# DNVT_box3rt.net
KiCad netlist of a schematic drawn in EAGLE
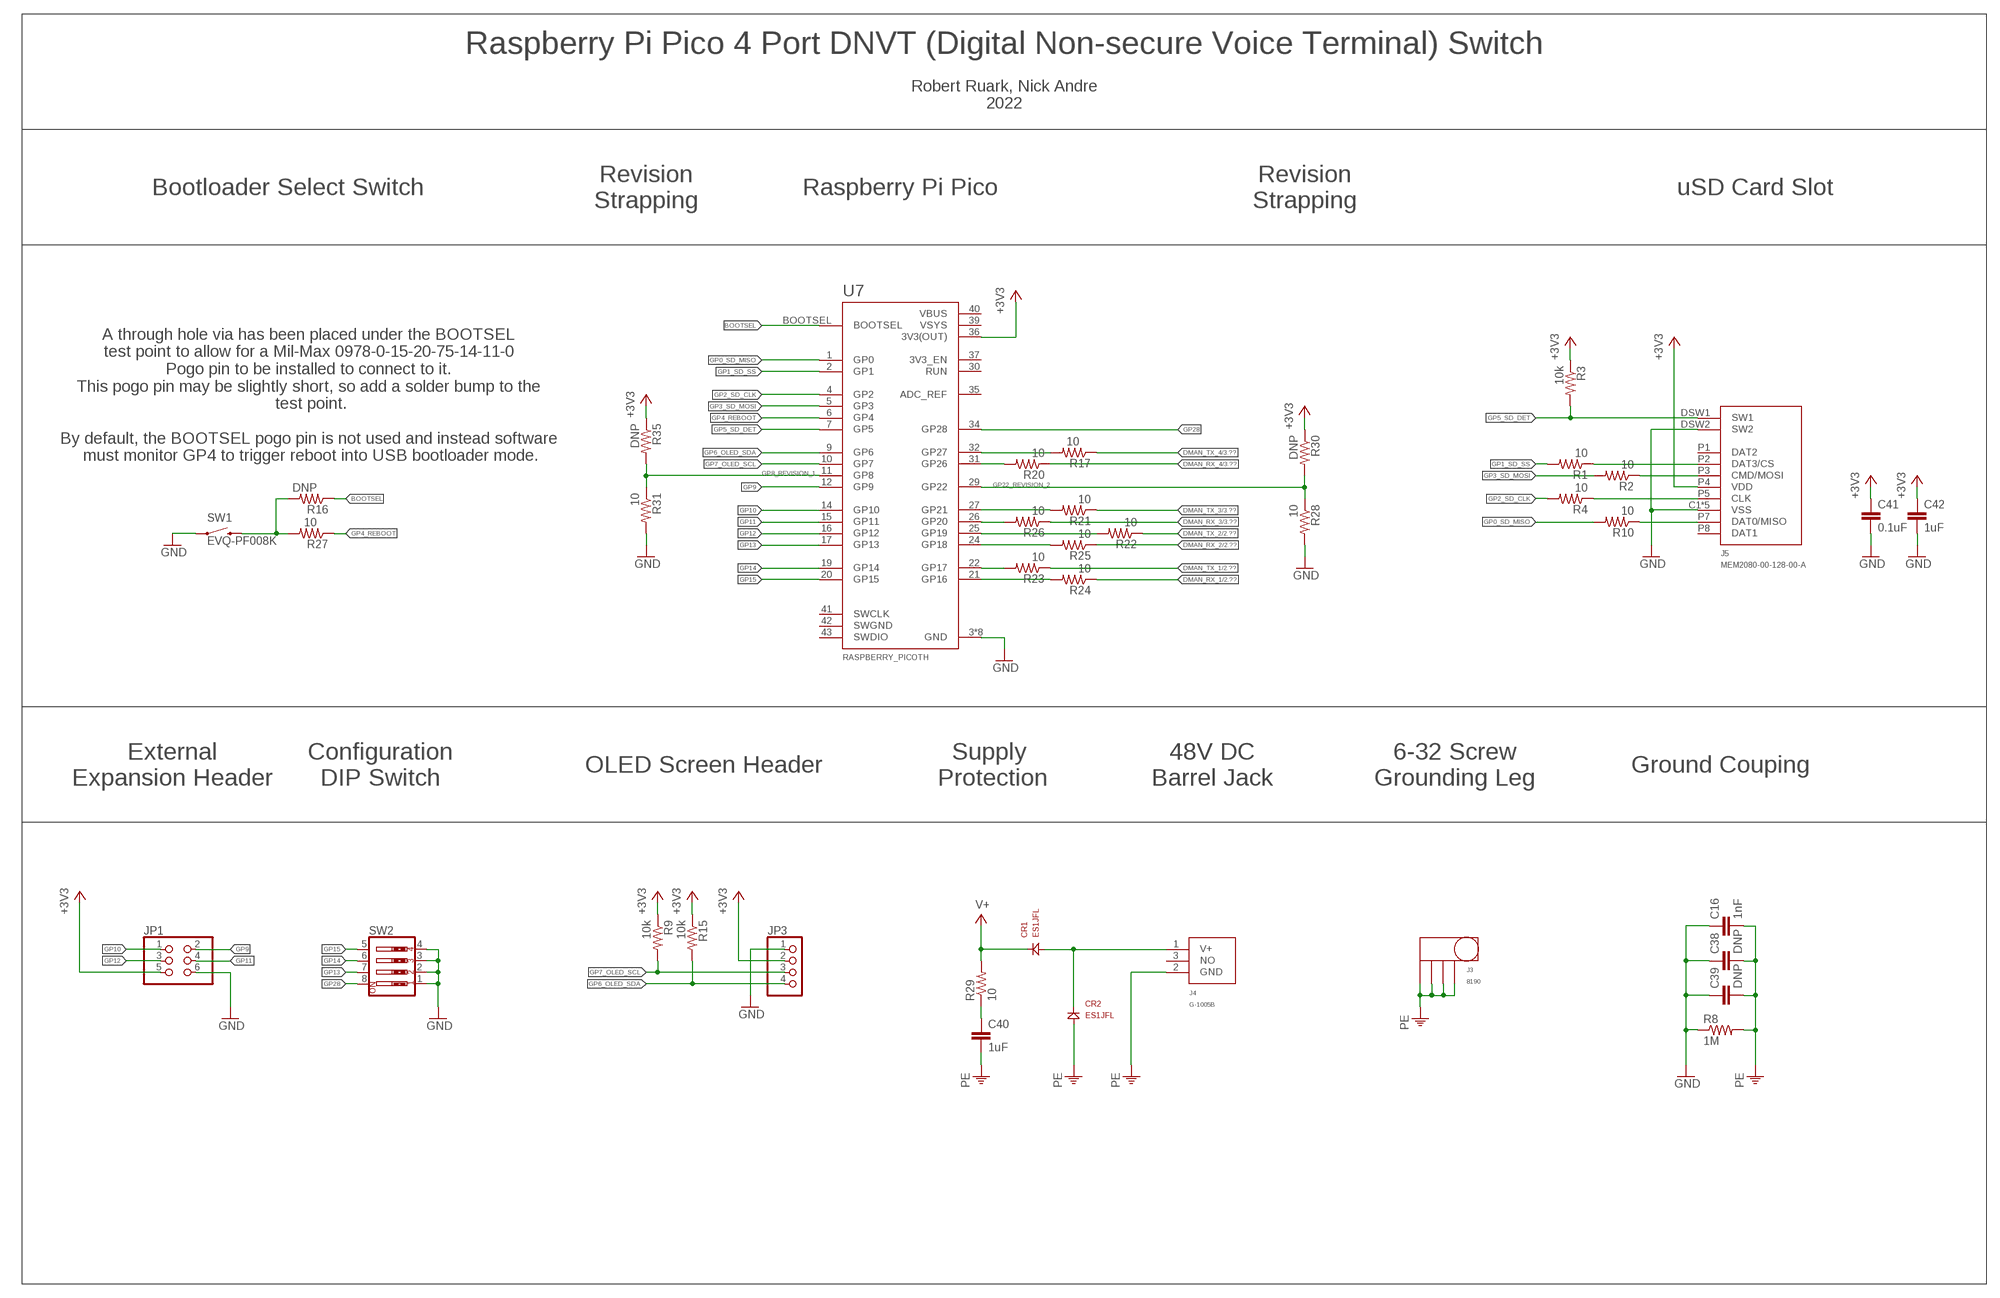
[diagram p0: schematic, sheet 1]
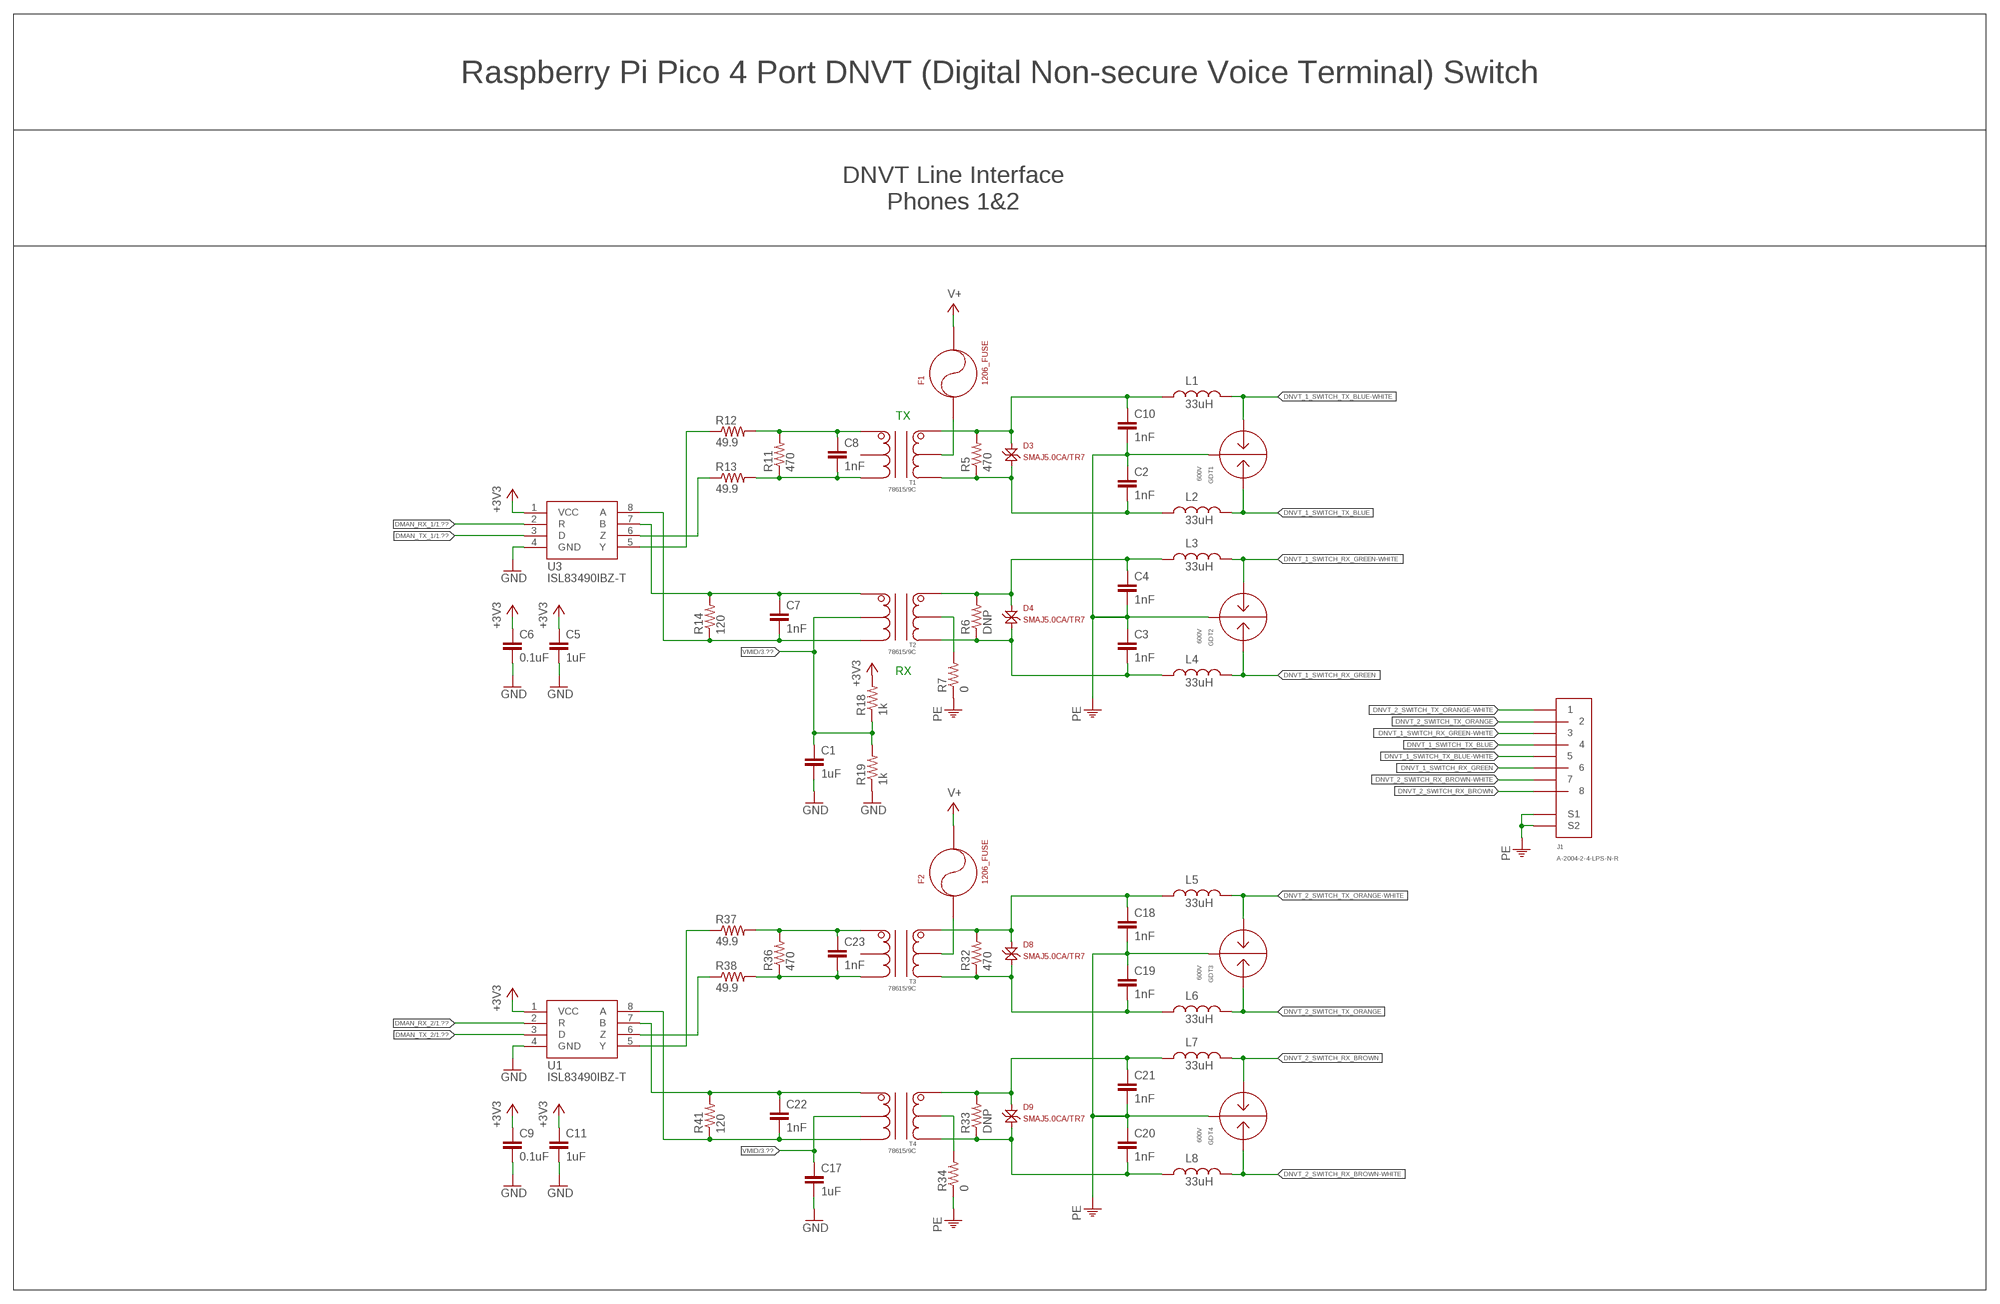
[diagram p1: schematic, sheet 2]
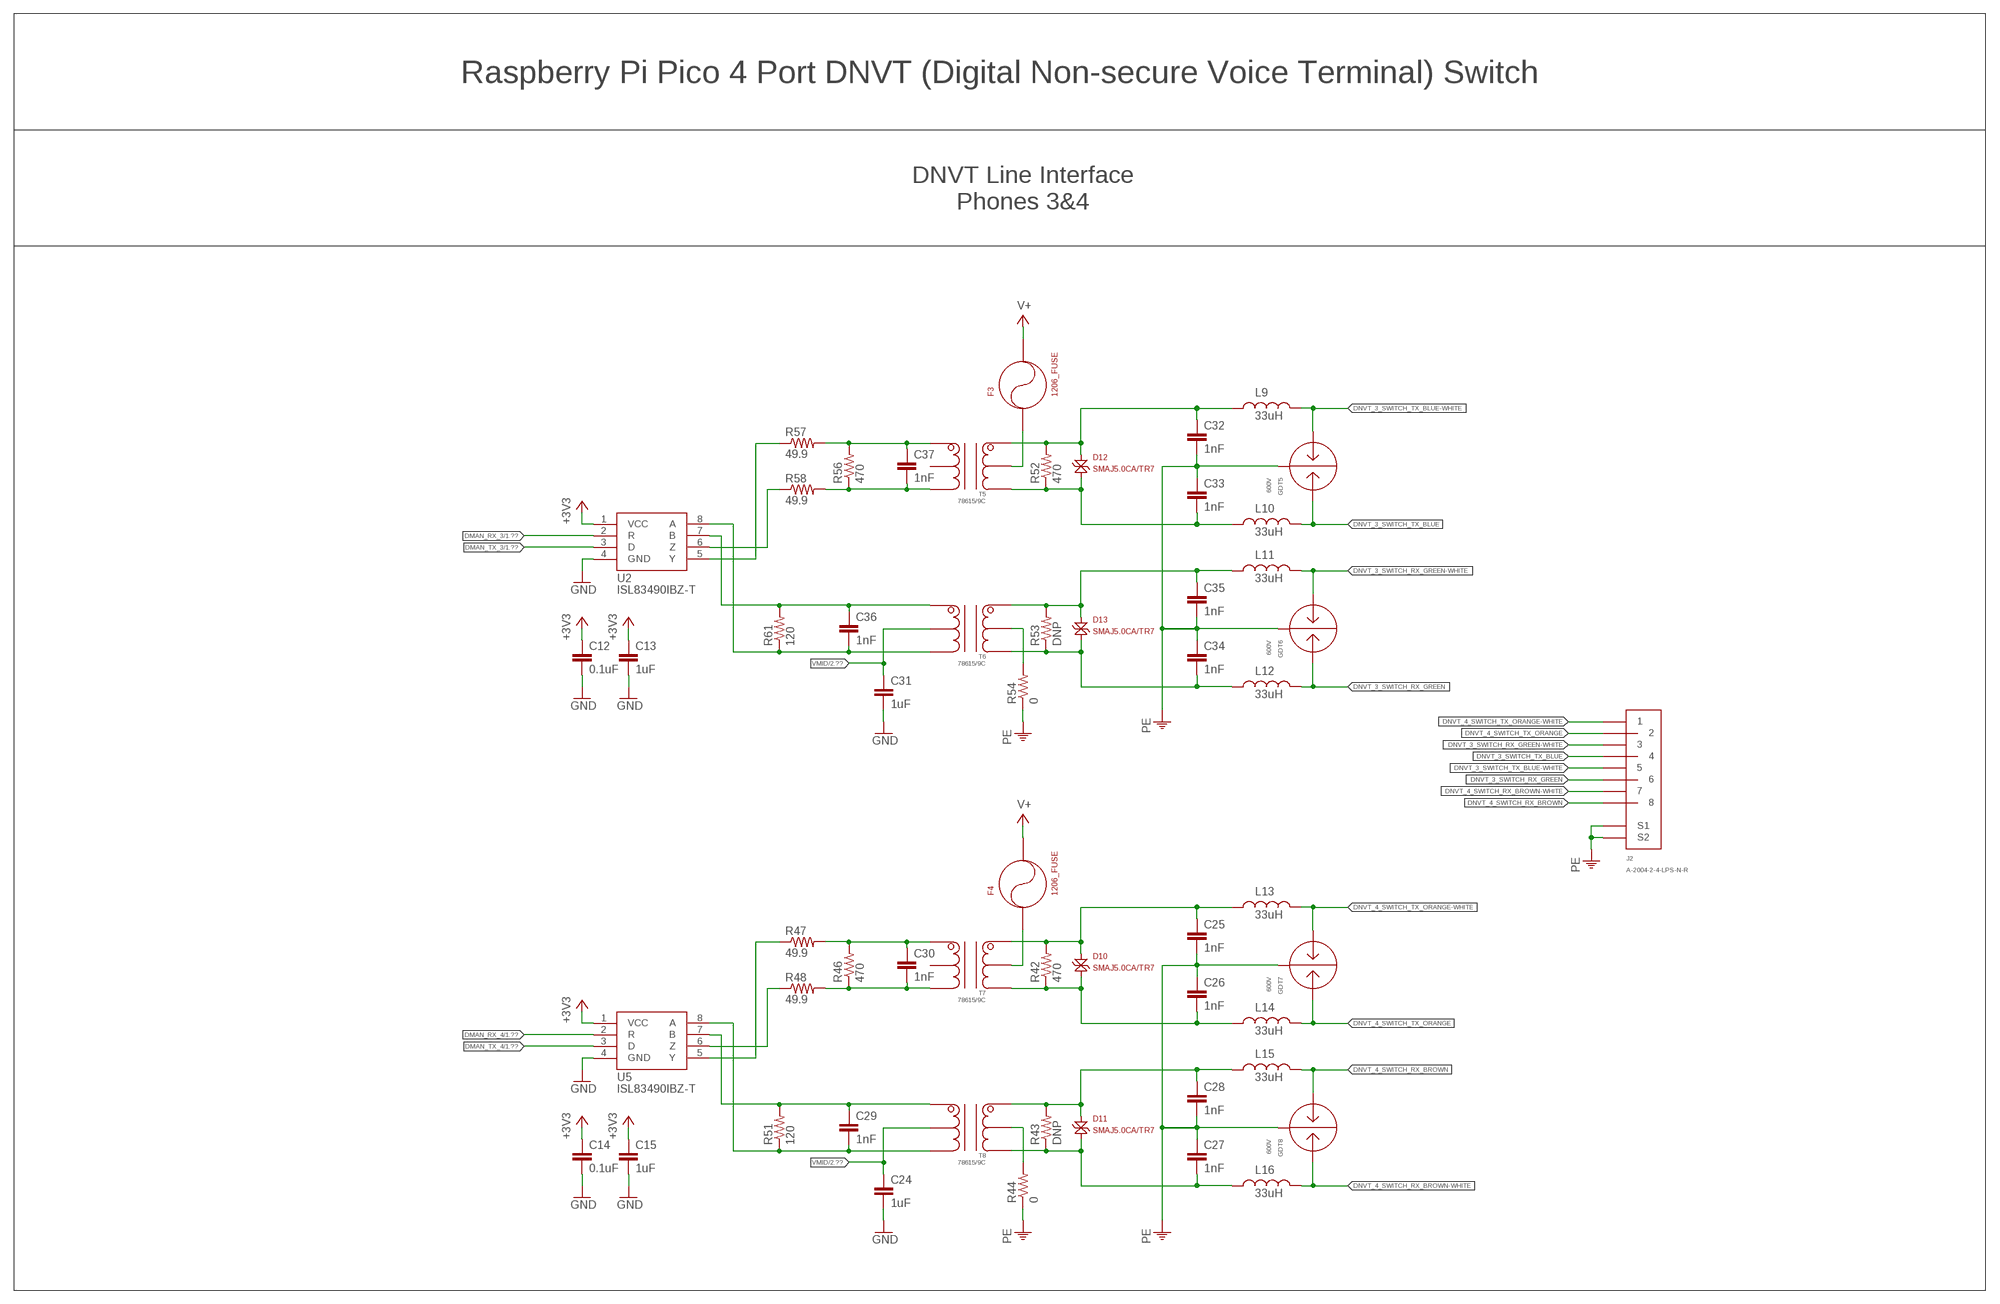
[diagram p2: schematic, sheet 3]

(export (version "E")
  (design (tool "Eeschema 10.0.6"))
  (components
    (comp (ref "C16")
      (value "1nF")
      (footprint "eagle-import:1206")
      (libsource (lib "eagle-import") (part "1206_CAPACITOR"))
    )
    (comp (ref "C38")
      (value "DNP")
      (footprint "eagle-import:1206")
      (libsource (lib "eagle-import") (part "1206_CAPACITOR"))
    )
    (comp (ref "C39")
      (value "DNP")
      (footprint "eagle-import:1206")
      (libsource (lib "eagle-import") (part "1206_CAPACITOR"))
    )
    (comp (ref "C40")
      (value "1uF")
      (footprint "eagle-import:1206")
      (libsource (lib "eagle-import") (part "1206_CAPACITOR"))
    )
    (comp (ref "C41")
      (value "0.1uF")
      (footprint "eagle-import:0603")
      (libsource (lib "eagle-import") (part "0603_CAPACITOR"))
    )
    (comp (ref "C42")
      (value "1uF")
      (footprint "eagle-import:0805")
      (libsource (lib "eagle-import") (part "0805_CAPACITOR"))
    )
    (comp (ref "CR1")
      (value "ES1JFL")
      (footprint "eagle-import:SOD123(AK)")
      (fields (field (name "PARTNO") "ES1JFLCT-ND"))
      (libsource (lib "eagle-import") (part "ES1JFL"))
    )
    (comp (ref "CR2")
      (value "ES1JFL")
      (footprint "eagle-import:SOD123(AK)")
      (fields (field (name "PARTNO") "ES1JFLCT-ND"))
      (libsource (lib "eagle-import") (part "ES1JFL"))
    )
    (comp (ref "J3")
      (value "8190")
      (footprint "eagle-import:7781")
      (fields (field (name "PARTNO") "36-8190-ND"))
      (libsource (lib "eagle-import") (part "8190"))
    )
    (comp (ref "J4")
      (value "G-1005B")
      (footprint "eagle-import:G-1005B")
      (fields (field (name "PARTNO") "1939-G-1005B-ND"))
      (libsource (lib "eagle-import") (part "G-1005B"))
    )
    (comp (ref "J5")
      (value "MEM2080-00-128-00-A")
      (footprint "eagle-import:MEM2080")
      (fields (field (name "PARTNO") "2073-MEM2080-00-128-00-ACT-ND"))
      (libsource (lib "eagle-import") (part "MEM2080-00-128-00-A"))
    )
    (comp (ref "JP1")
      (value "PINHD-2X3/90")
      (footprint "eagle-import:2X03_90")
      (libsource (lib "eagle-import") (part "PINHD-2X3/90"))
    )
    (comp (ref "JP3")
      (value "PINHD-1X4")
      (footprint "eagle-import:1X04")
      (libsource (lib "eagle-import") (part "PINHD-1X4"))
    )
    (comp (ref "R1")
      (value "10")
      (footprint "eagle-import:0603")
      (libsource (lib "eagle-import") (part "0603_RESISTOR"))
    )
    (comp (ref "R2")
      (value "10")
      (footprint "eagle-import:0603")
      (libsource (lib "eagle-import") (part "0603_RESISTOR"))
    )
    (comp (ref "R3")
      (value "10k")
      (footprint "eagle-import:0603")
      (libsource (lib "eagle-import") (part "0603_RESISTOR"))
    )
    (comp (ref "R4")
      (value "10")
      (footprint "eagle-import:0603")
      (libsource (lib "eagle-import") (part "0603_RESISTOR"))
    )
    (comp (ref "R8")
      (value "1M")
      (footprint "eagle-import:1206")
      (libsource (lib "eagle-import") (part "1206_RESISTOR"))
    )
    (comp (ref "R9")
      (value "10k")
      (footprint "eagle-import:0603")
      (libsource (lib "eagle-import") (part "0603_RESISTOR"))
    )
    (comp (ref "R10")
      (value "10")
      (footprint "eagle-import:0603")
      (libsource (lib "eagle-import") (part "0603_RESISTOR"))
    )
    (comp (ref "R15")
      (value "10k")
      (footprint "eagle-import:0603")
      (libsource (lib "eagle-import") (part "0603_RESISTOR"))
    )
    (comp (ref "R16")
      (value "DNP")
      (footprint "eagle-import:0603")
      (libsource (lib "eagle-import") (part "0603_RESISTOR"))
    )
    (comp (ref "R17")
      (value "10")
      (footprint "eagle-import:0603")
      (libsource (lib "eagle-import") (part "0603_RESISTOR"))
    )
    (comp (ref "R20")
      (value "10")
      (footprint "eagle-import:0603")
      (libsource (lib "eagle-import") (part "0603_RESISTOR"))
    )
    (comp (ref "R21")
      (value "10")
      (footprint "eagle-import:0603")
      (libsource (lib "eagle-import") (part "0603_RESISTOR"))
    )
    (comp (ref "R22")
      (value "10")
      (footprint "eagle-import:0603")
      (libsource (lib "eagle-import") (part "0603_RESISTOR"))
    )
    (comp (ref "R23")
      (value "10")
      (footprint "eagle-import:0603")
      (libsource (lib "eagle-import") (part "0603_RESISTOR"))
    )
    (comp (ref "R24")
      (value "10")
      (footprint "eagle-import:0603")
      (libsource (lib "eagle-import") (part "0603_RESISTOR"))
    )
    (comp (ref "R25")
      (value "10")
      (footprint "eagle-import:0603")
      (libsource (lib "eagle-import") (part "0603_RESISTOR"))
    )
    (comp (ref "R26")
      (value "10")
      (footprint "eagle-import:0603")
      (libsource (lib "eagle-import") (part "0603_RESISTOR"))
    )
    (comp (ref "R27")
      (value "10")
      (footprint "eagle-import:0603")
      (libsource (lib "eagle-import") (part "0603_RESISTOR"))
    )
    (comp (ref "R28")
      (value "10")
      (footprint "eagle-import:0603")
      (libsource (lib "eagle-import") (part "0603_RESISTOR"))
    )
    (comp (ref "R29")
      (value "10")
      (footprint "eagle-import:1206")
      (libsource (lib "eagle-import") (part "1206_RESISTOR"))
    )
    (comp (ref "R30")
      (value "DNP")
      (footprint "eagle-import:0603")
      (libsource (lib "eagle-import") (part "0603_RESISTOR"))
    )
    (comp (ref "R31")
      (value "10")
      (footprint "eagle-import:0603")
      (libsource (lib "eagle-import") (part "0603_RESISTOR"))
    )
    (comp (ref "R35")
      (value "DNP")
      (footprint "eagle-import:0603")
      (libsource (lib "eagle-import") (part "0603_RESISTOR"))
    )
    (comp (ref "SW1")
      (value "EVQ-PF008K")
      (footprint "eagle-import:EVQ-PF008K")
      (fields (field (name "PARTNO") "P10880S-ND"))
      (libsource (lib "eagle-import") (part "EVQ-PF008K"))
    )
    (comp (ref "SW2")
      (value "SW_DIP-4")
      (footprint "eagle-import:EDG-04")
      (libsource (lib "eagle-import") (part "SW_DIP-4"))
    )
    (comp (ref "U7")
      (value "RASPBERRY_PICOTH")
      (footprint "eagle-import:PICO-PKG-TH")
      (libsource (lib "eagle-import") (part "RASPBERRY_PICOTH"))
    )
    (comp (ref "C1")
      (value "1uF")
      (footprint "eagle-import:0805")
      (libsource (lib "eagle-import") (part "0805_CAPACITOR"))
    )
    (comp (ref "C2")
      (value "1nF")
      (footprint "eagle-import:0805")
      (libsource (lib "eagle-import") (part "0805_CAPACITOR"))
    )
    (comp (ref "C3")
      (value "1nF")
      (footprint "eagle-import:0805")
      (libsource (lib "eagle-import") (part "0805_CAPACITOR"))
    )
    (comp (ref "C4")
      (value "1nF")
      (footprint "eagle-import:0805")
      (libsource (lib "eagle-import") (part "0805_CAPACITOR"))
    )
    (comp (ref "C5")
      (value "1uF")
      (footprint "eagle-import:0805")
      (libsource (lib "eagle-import") (part "0805_CAPACITOR"))
    )
    (comp (ref "C6")
      (value "0.1uF")
      (footprint "eagle-import:0603")
      (libsource (lib "eagle-import") (part "0603_CAPACITOR"))
    )
    (comp (ref "C7")
      (value "1nF")
      (footprint "eagle-import:0805")
      (libsource (lib "eagle-import") (part "0805_CAPACITOR"))
    )
    (comp (ref "C8")
      (value "1nF")
      (footprint "eagle-import:0805")
      (libsource (lib "eagle-import") (part "0805_CAPACITOR"))
    )
    (comp (ref "C9")
      (value "0.1uF")
      (footprint "eagle-import:0603")
      (libsource (lib "eagle-import") (part "0603_CAPACITOR"))
    )
    (comp (ref "C10")
      (value "1nF")
      (footprint "eagle-import:0805")
      (libsource (lib "eagle-import") (part "0805_CAPACITOR"))
    )
    (comp (ref "C11")
      (value "1uF")
      (footprint "eagle-import:0805")
      (libsource (lib "eagle-import") (part "0805_CAPACITOR"))
    )
    (comp (ref "C17")
      (value "1uF")
      (footprint "eagle-import:0805")
      (libsource (lib "eagle-import") (part "0805_CAPACITOR"))
    )
    (comp (ref "C18")
      (value "1nF")
      (footprint "eagle-import:0805")
      (libsource (lib "eagle-import") (part "0805_CAPACITOR"))
    )
    (comp (ref "C19")
      (value "1nF")
      (footprint "eagle-import:0805")
      (libsource (lib "eagle-import") (part "0805_CAPACITOR"))
    )
    (comp (ref "C20")
      (value "1nF")
      (footprint "eagle-import:0805")
      (libsource (lib "eagle-import") (part "0805_CAPACITOR"))
    )
    (comp (ref "C21")
      (value "1nF")
      (footprint "eagle-import:0805")
      (libsource (lib "eagle-import") (part "0805_CAPACITOR"))
    )
    (comp (ref "C22")
      (value "1nF")
      (footprint "eagle-import:0805")
      (libsource (lib "eagle-import") (part "0805_CAPACITOR"))
    )
    (comp (ref "C23")
      (value "1nF")
      (footprint "eagle-import:0805")
      (libsource (lib "eagle-import") (part "0805_CAPACITOR"))
    )
    (comp (ref "D3")
      (value "SMAJ5.0CA/TR7")
      (footprint "eagle-import:DO-214AC_NO_POL")
      (libsource (lib "eagle-import") (part "SMAJ5.0CA/TR7"))
    )
    (comp (ref "D4")
      (value "SMAJ5.0CA/TR7")
      (footprint "eagle-import:DO-214AC_NO_POL")
      (libsource (lib "eagle-import") (part "SMAJ5.0CA/TR7"))
    )
    (comp (ref "D8")
      (value "SMAJ5.0CA/TR7")
      (footprint "eagle-import:DO-214AC_NO_POL")
      (libsource (lib "eagle-import") (part "SMAJ5.0CA/TR7"))
    )
    (comp (ref "D9")
      (value "SMAJ5.0CA/TR7")
      (footprint "eagle-import:DO-214AC_NO_POL")
      (libsource (lib "eagle-import") (part "SMAJ5.0CA/TR7"))
    )
    (comp (ref "F1")
      (value "1206_FUSE")
      (footprint "eagle-import:1206")
      (libsource (lib "eagle-import") (part "1206_FUSE"))
    )
    (comp (ref "F2")
      (value "1206_FUSE")
      (footprint "eagle-import:1206")
      (libsource (lib "eagle-import") (part "1206_FUSE"))
    )
    (comp (ref "GDT1")
      (value "600V")
      (footprint "eagle-import:2036_GDT")
      (fields (field (name "PARTNO") "2036-60-SM-RPLFCT-ND"))
      (libsource (lib "eagle-import") (part "2036-60-SM-RPLF"))
    )
    (comp (ref "GDT2")
      (value "600V")
      (footprint "eagle-import:2036_GDT")
      (fields (field (name "PARTNO") "2036-60-SM-RPLFCT-ND"))
      (libsource (lib "eagle-import") (part "2036-60-SM-RPLF"))
    )
    (comp (ref "GDT3")
      (value "600V")
      (footprint "eagle-import:2036_GDT")
      (fields (field (name "PARTNO") "2036-60-SM-RPLFCT-ND"))
      (libsource (lib "eagle-import") (part "2036-60-SM-RPLF"))
    )
    (comp (ref "GDT4")
      (value "600V")
      (footprint "eagle-import:2036_GDT")
      (fields (field (name "PARTNO") "2036-60-SM-RPLFCT-ND"))
      (libsource (lib "eagle-import") (part "2036-60-SM-RPLF"))
    )
    (comp (ref "J1")
      (value "A-2004-2-4-LPS-N-R")
      (footprint "eagle-import:A-2004-2-4-LPS-N-R")
      (fields (field (name "PARTNO") "AE10387-ND"))
      (libsource (lib "eagle-import") (part "A-2004-2-4-LPS-N-R"))
    )
    (comp (ref "L1")
      (value "33uH")
      (footprint "eagle-import:SDR0403")
      (fields (field (name "PARTNO") "SDR0403-330KLCT-ND"))
      (libsource (lib "eagle-import") (part "SDR0403-330KL"))
    )
    (comp (ref "L2")
      (value "33uH")
      (footprint "eagle-import:SDR0403")
      (fields (field (name "PARTNO") "SDR0403-330KLCT-ND"))
      (libsource (lib "eagle-import") (part "SDR0403-330KL"))
    )
    (comp (ref "L3")
      (value "33uH")
      (footprint "eagle-import:SDR0403")
      (fields (field (name "PARTNO") "SDR0403-330KLCT-ND"))
      (libsource (lib "eagle-import") (part "SDR0403-330KL"))
    )
    (comp (ref "L4")
      (value "33uH")
      (footprint "eagle-import:SDR0403")
      (fields (field (name "PARTNO") "SDR0403-330KLCT-ND"))
      (libsource (lib "eagle-import") (part "SDR0403-330KL"))
    )
    (comp (ref "L5")
      (value "33uH")
      (footprint "eagle-import:SDR0403")
      (fields (field (name "PARTNO") "SDR0403-330KLCT-ND"))
      (libsource (lib "eagle-import") (part "SDR0403-330KL"))
    )
    (comp (ref "L6")
      (value "33uH")
      (footprint "eagle-import:SDR0403")
      (fields (field (name "PARTNO") "SDR0403-330KLCT-ND"))
      (libsource (lib "eagle-import") (part "SDR0403-330KL"))
    )
    (comp (ref "L7")
      (value "33uH")
      (footprint "eagle-import:SDR0403")
      (fields (field (name "PARTNO") "SDR0403-330KLCT-ND"))
      (libsource (lib "eagle-import") (part "SDR0403-330KL"))
    )
    (comp (ref "L8")
      (value "33uH")
      (footprint "eagle-import:SDR0403")
      (fields (field (name "PARTNO") "SDR0403-330KLCT-ND"))
      (libsource (lib "eagle-import") (part "SDR0403-330KL"))
    )
    (comp (ref "R5")
      (value "470")
      (footprint "eagle-import:R0805")
      (libsource (lib "eagle-import") (part "R-US_R0805"))
    )
    (comp (ref "R6")
      (value "DNP")
      (footprint "eagle-import:R0805")
      (libsource (lib "eagle-import") (part "R-US_R0805"))
    )
    (comp (ref "R7")
      (value "0")
      (footprint "eagle-import:R0805")
      (libsource (lib "eagle-import") (part "R-US_R0805"))
    )
    (comp (ref "R11")
      (value "470")
      (footprint "eagle-import:R0805")
      (libsource (lib "eagle-import") (part "R-US_R0805"))
    )
    (comp (ref "R12")
      (value "49.9")
      (footprint "eagle-import:R0805")
      (libsource (lib "eagle-import") (part "R-US_R0805"))
    )
    (comp (ref "R13")
      (value "49.9")
      (footprint "eagle-import:R0805")
      (libsource (lib "eagle-import") (part "R-US_R0805"))
    )
    (comp (ref "R14")
      (value "120")
      (footprint "eagle-import:1206")
      (libsource (lib "eagle-import") (part "1206_RESISTOR"))
    )
    (comp (ref "R18")
      (value "1k")
      (footprint "eagle-import:0603")
      (libsource (lib "eagle-import") (part "0603_RESISTOR"))
    )
    (comp (ref "R19")
      (value "1k")
      (footprint "eagle-import:0603")
      (libsource (lib "eagle-import") (part "0603_RESISTOR"))
    )
    (comp (ref "R32")
      (value "470")
      (footprint "eagle-import:R0805")
      (libsource (lib "eagle-import") (part "R-US_R0805"))
    )
    (comp (ref "R33")
      (value "DNP")
      (footprint "eagle-import:R0805")
      (libsource (lib "eagle-import") (part "R-US_R0805"))
    )
    (comp (ref "R34")
      (value "0")
      (footprint "eagle-import:R0805")
      (libsource (lib "eagle-import") (part "R-US_R0805"))
    )
    (comp (ref "R36")
      (value "470")
      (footprint "eagle-import:R0805")
      (libsource (lib "eagle-import") (part "R-US_R0805"))
    )
    (comp (ref "R37")
      (value "49.9")
      (footprint "eagle-import:R0805")
      (libsource (lib "eagle-import") (part "R-US_R0805"))
    )
    (comp (ref "R38")
      (value "49.9")
      (footprint "eagle-import:R0805")
      (libsource (lib "eagle-import") (part "R-US_R0805"))
    )
    (comp (ref "R41")
      (value "120")
      (footprint "eagle-import:1206")
      (libsource (lib "eagle-import") (part "1206_RESISTOR"))
    )
    (comp (ref "T1")
      (value "78615/9C")
      (footprint "eagle-import:786T")
      (libsource (lib "eagle-import") (part "78615/9C"))
    )
    (comp (ref "T2")
      (value "78615/9C")
      (footprint "eagle-import:786T")
      (libsource (lib "eagle-import") (part "78615/9C"))
    )
    (comp (ref "T3")
      (value "78615/9C")
      (footprint "eagle-import:786T")
      (libsource (lib "eagle-import") (part "78615/9C"))
    )
    (comp (ref "T4")
      (value "78615/9C")
      (footprint "eagle-import:786T")
      (libsource (lib "eagle-import") (part "78615/9C"))
    )
    (comp (ref "U1")
      (value "ISL83490IBZ-T")
      (footprint "eagle-import:SOIC8")
      (fields (field (name "PARTNO") "ISL83490IBZ-TCT-ND"))
      (libsource (lib "eagle-import") (part "ISL83490IBZ-T"))
    )
    (comp (ref "U3")
      (value "ISL83490IBZ-T")
      (footprint "eagle-import:SOIC8")
      (fields (field (name "PARTNO") "ISL83490IBZ-TCT-ND"))
      (libsource (lib "eagle-import") (part "ISL83490IBZ-T"))
    )
    (comp (ref "C12")
      (value "0.1uF")
      (footprint "eagle-import:0603")
      (libsource (lib "eagle-import") (part "0603_CAPACITOR"))
    )
    (comp (ref "C13")
      (value "1uF")
      (footprint "eagle-import:0805")
      (libsource (lib "eagle-import") (part "0805_CAPACITOR"))
    )
    (comp (ref "C14")
      (value "0.1uF")
      (footprint "eagle-import:0603")
      (libsource (lib "eagle-import") (part "0603_CAPACITOR"))
    )
    (comp (ref "C15")
      (value "1uF")
      (footprint "eagle-import:0805")
      (libsource (lib "eagle-import") (part "0805_CAPACITOR"))
    )
    (comp (ref "C24")
      (value "1uF")
      (footprint "eagle-import:0805")
      (libsource (lib "eagle-import") (part "0805_CAPACITOR"))
    )
    (comp (ref "C25")
      (value "1nF")
      (footprint "eagle-import:0805")
      (libsource (lib "eagle-import") (part "0805_CAPACITOR"))
    )
    (comp (ref "C26")
      (value "1nF")
      (footprint "eagle-import:0805")
      (libsource (lib "eagle-import") (part "0805_CAPACITOR"))
    )
    (comp (ref "C27")
      (value "1nF")
      (footprint "eagle-import:0805")
      (libsource (lib "eagle-import") (part "0805_CAPACITOR"))
    )
    (comp (ref "C28")
      (value "1nF")
      (footprint "eagle-import:0805")
      (libsource (lib "eagle-import") (part "0805_CAPACITOR"))
    )
    (comp (ref "C29")
      (value "1nF")
      (footprint "eagle-import:0805")
      (libsource (lib "eagle-import") (part "0805_CAPACITOR"))
    )
    (comp (ref "C30")
      (value "1nF")
      (footprint "eagle-import:0805")
      (libsource (lib "eagle-import") (part "0805_CAPACITOR"))
    )
    (comp (ref "C31")
      (value "1uF")
      (footprint "eagle-import:0805")
      (libsource (lib "eagle-import") (part "0805_CAPACITOR"))
    )
    (comp (ref "C32")
      (value "1nF")
      (footprint "eagle-import:0805")
      (libsource (lib "eagle-import") (part "0805_CAPACITOR"))
    )
    (comp (ref "C33")
      (value "1nF")
      (footprint "eagle-import:0805")
      (libsource (lib "eagle-import") (part "0805_CAPACITOR"))
    )
    (comp (ref "C34")
      (value "1nF")
      (footprint "eagle-import:0805")
      (libsource (lib "eagle-import") (part "0805_CAPACITOR"))
    )
    (comp (ref "C35")
      (value "1nF")
      (footprint "eagle-import:0805")
      (libsource (lib "eagle-import") (part "0805_CAPACITOR"))
    )
    (comp (ref "C36")
      (value "1nF")
      (footprint "eagle-import:0805")
      (libsource (lib "eagle-import") (part "0805_CAPACITOR"))
    )
    (comp (ref "C37")
      (value "1nF")
      (footprint "eagle-import:0805")
      (libsource (lib "eagle-import") (part "0805_CAPACITOR"))
    )
    (comp (ref "D10")
      (value "SMAJ5.0CA/TR7")
      (footprint "eagle-import:DO-214AC_NO_POL")
      (libsource (lib "eagle-import") (part "SMAJ5.0CA/TR7"))
    )
    (comp (ref "D11")
      (value "SMAJ5.0CA/TR7")
      (footprint "eagle-import:DO-214AC_NO_POL")
      (libsource (lib "eagle-import") (part "SMAJ5.0CA/TR7"))
    )
    (comp (ref "D12")
      (value "SMAJ5.0CA/TR7")
      (footprint "eagle-import:DO-214AC_NO_POL")
      (libsource (lib "eagle-import") (part "SMAJ5.0CA/TR7"))
    )
    (comp (ref "D13")
      (value "SMAJ5.0CA/TR7")
      (footprint "eagle-import:DO-214AC_NO_POL")
      (libsource (lib "eagle-import") (part "SMAJ5.0CA/TR7"))
    )
    (comp (ref "F3")
      (value "1206_FUSE")
      (footprint "eagle-import:1206")
      (libsource (lib "eagle-import") (part "1206_FUSE"))
    )
    (comp (ref "F4")
      (value "1206_FUSE")
      (footprint "eagle-import:1206")
      (libsource (lib "eagle-import") (part "1206_FUSE"))
    )
    (comp (ref "GDT5")
      (value "600V")
      (footprint "eagle-import:2036_GDT")
      (fields (field (name "PARTNO") "2036-60-SM-RPLFCT-ND"))
      (libsource (lib "eagle-import") (part "2036-60-SM-RPLF"))
    )
    (comp (ref "GDT6")
      (value "600V")
      (footprint "eagle-import:2036_GDT")
      (fields (field (name "PARTNO") "2036-60-SM-RPLFCT-ND"))
      (libsource (lib "eagle-import") (part "2036-60-SM-RPLF"))
    )
    (comp (ref "GDT7")
      (value "600V")
      (footprint "eagle-import:2036_GDT")
      (fields (field (name "PARTNO") "2036-60-SM-RPLFCT-ND"))
      (libsource (lib "eagle-import") (part "2036-60-SM-RPLF"))
    )
    (comp (ref "GDT8")
      (value "600V")
      (footprint "eagle-import:2036_GDT")
      (fields (field (name "PARTNO") "2036-60-SM-RPLFCT-ND"))
      (libsource (lib "eagle-import") (part "2036-60-SM-RPLF"))
    )
    (comp (ref "J2")
      (value "A-2004-2-4-LPS-N-R")
      (footprint "eagle-import:A-2004-2-4-LPS-N-R")
      (fields (field (name "PARTNO") "AE10387-ND"))
      (libsource (lib "eagle-import") (part "A-2004-2-4-LPS-N-R"))
    )
    (comp (ref "L9")
      (value "33uH")
      (footprint "eagle-import:SDR0403")
      (fields (field (name "PARTNO") "SDR0403-330KLCT-ND"))
      (libsource (lib "eagle-import") (part "SDR0403-330KL"))
    )
    (comp (ref "L10")
      (value "33uH")
      (footprint "eagle-import:SDR0403")
      (fields (field (name "PARTNO") "SDR0403-330KLCT-ND"))
      (libsource (lib "eagle-import") (part "SDR0403-330KL"))
    )
    (comp (ref "L11")
      (value "33uH")
      (footprint "eagle-import:SDR0403")
      (fields (field (name "PARTNO") "SDR0403-330KLCT-ND"))
      (libsource (lib "eagle-import") (part "SDR0403-330KL"))
    )
    (comp (ref "L12")
      (value "33uH")
      (footprint "eagle-import:SDR0403")
      (fields (field (name "PARTNO") "SDR0403-330KLCT-ND"))
      (libsource (lib "eagle-import") (part "SDR0403-330KL"))
    )
    (comp (ref "L13")
      (value "33uH")
      (footprint "eagle-import:SDR0403")
      (fields (field (name "PARTNO") "SDR0403-330KLCT-ND"))
      (libsource (lib "eagle-import") (part "SDR0403-330KL"))
    )
    (comp (ref "L14")
      (value "33uH")
      (footprint "eagle-import:SDR0403")
      (fields (field (name "PARTNO") "SDR0403-330KLCT-ND"))
      (libsource (lib "eagle-import") (part "SDR0403-330KL"))
    )
    (comp (ref "L15")
      (value "33uH")
      (footprint "eagle-import:SDR0403")
      (fields (field (name "PARTNO") "SDR0403-330KLCT-ND"))
      (libsource (lib "eagle-import") (part "SDR0403-330KL"))
    )
    (comp (ref "L16")
      (value "33uH")
      (footprint "eagle-import:SDR0403")
      (fields (field (name "PARTNO") "SDR0403-330KLCT-ND"))
      (libsource (lib "eagle-import") (part "SDR0403-330KL"))
    )
    (comp (ref "R42")
      (value "470")
      (footprint "eagle-import:R0805")
      (libsource (lib "eagle-import") (part "R-US_R0805"))
    )
    (comp (ref "R43")
      (value "DNP")
      (footprint "eagle-import:R0805")
      (libsource (lib "eagle-import") (part "R-US_R0805"))
    )
    (comp (ref "R44")
      (value "0")
      (footprint "eagle-import:R0805")
      (libsource (lib "eagle-import") (part "R-US_R0805"))
    )
    (comp (ref "R46")
      (value "470")
      (footprint "eagle-import:R0805")
      (libsource (lib "eagle-import") (part "R-US_R0805"))
    )
    (comp (ref "R47")
      (value "49.9")
      (footprint "eagle-import:R0805")
      (libsource (lib "eagle-import") (part "R-US_R0805"))
    )
    (comp (ref "R48")
      (value "49.9")
      (footprint "eagle-import:R0805")
      (libsource (lib "eagle-import") (part "R-US_R0805"))
    )
    (comp (ref "R51")
      (value "120")
      (footprint "eagle-import:1206")
      (libsource (lib "eagle-import") (part "1206_RESISTOR"))
    )
    (comp (ref "R52")
      (value "470")
      (footprint "eagle-import:R0805")
      (libsource (lib "eagle-import") (part "R-US_R0805"))
    )
    (comp (ref "R53")
      (value "DNP")
      (footprint "eagle-import:R0805")
      (libsource (lib "eagle-import") (part "R-US_R0805"))
    )
    (comp (ref "R54")
      (value "0")
      (footprint "eagle-import:R0805")
      (libsource (lib "eagle-import") (part "R-US_R0805"))
    )
    (comp (ref "R56")
      (value "470")
      (footprint "eagle-import:R0805")
      (libsource (lib "eagle-import") (part "R-US_R0805"))
    )
    (comp (ref "R57")
      (value "49.9")
      (footprint "eagle-import:R0805")
      (libsource (lib "eagle-import") (part "R-US_R0805"))
    )
    (comp (ref "R58")
      (value "49.9")
      (footprint "eagle-import:R0805")
      (libsource (lib "eagle-import") (part "R-US_R0805"))
    )
    (comp (ref "R61")
      (value "120")
      (footprint "eagle-import:1206")
      (libsource (lib "eagle-import") (part "1206_RESISTOR"))
    )
    (comp (ref "T5")
      (value "78615/9C")
      (footprint "eagle-import:786T")
      (libsource (lib "eagle-import") (part "78615/9C"))
    )
    (comp (ref "T6")
      (value "78615/9C")
      (footprint "eagle-import:786T")
      (libsource (lib "eagle-import") (part "78615/9C"))
    )
    (comp (ref "T7")
      (value "78615/9C")
      (footprint "eagle-import:786T")
      (libsource (lib "eagle-import") (part "78615/9C"))
    )
    (comp (ref "T8")
      (value "78615/9C")
      (footprint "eagle-import:786T")
      (libsource (lib "eagle-import") (part "78615/9C"))
    )
    (comp (ref "U2")
      (value "ISL83490IBZ-T")
      (footprint "eagle-import:SOIC8")
      (fields (field (name "PARTNO") "ISL83490IBZ-TCT-ND"))
      (libsource (lib "eagle-import") (part "ISL83490IBZ-T"))
    )
    (comp (ref "U5")
      (value "ISL83490IBZ-T")
      (footprint "eagle-import:SOIC8")
      (fields (field (name "PARTNO") "ISL83490IBZ-TCT-ND"))
      (libsource (lib "eagle-import") (part "ISL83490IBZ-T"))
    )
  )
  (nets
    (net (code "1") (name "+3V3") (class "Default")
      (node (ref "C11") (pin "1") (pinfunction "1_1") (pintype "passive"))
      (node (ref "C12") (pin "1") (pinfunction "1_1") (pintype "passive"))
      (node (ref "C13") (pin "1") (pinfunction "1_1") (pintype "passive"))
      (node (ref "C14") (pin "1") (pinfunction "1_1") (pintype "passive"))
      (node (ref "C15") (pin "1") (pinfunction "1_1") (pintype "passive"))
      (node (ref "C41") (pin "1") (pinfunction "1_1") (pintype "passive"))
      (node (ref "C42") (pin "1") (pinfunction "1_1") (pintype "passive"))
      (node (ref "C5") (pin "1") (pinfunction "1_1") (pintype "passive"))
      (node (ref "C6") (pin "1") (pinfunction "1_1") (pintype "passive"))
      (node (ref "C9") (pin "1") (pinfunction "1_1") (pintype "passive"))
      (node (ref "J5") (pin "P4") (pinfunction "VDD_P4") (pintype "bidirectional"))
      (node (ref "JP1") (pin "5") (pinfunction "5_5") (pintype "passive"))
      (node (ref "JP3") (pin "2") (pinfunction "2_2") (pintype "passive"))
      (node (ref "R15") (pin "1") (pinfunction "1_1") (pintype "passive"))
      (node (ref "R18") (pin "2") (pinfunction "2_2") (pintype "passive"))
      (node (ref "R3") (pin "1") (pinfunction "1_1") (pintype "passive"))
      (node (ref "R30") (pin "1") (pinfunction "1_1") (pintype "passive"))
      (node (ref "R35") (pin "1") (pinfunction "1_1") (pintype "passive"))
      (node (ref "R9") (pin "1") (pinfunction "1_1") (pintype "passive"))
      (node (ref "U1") (pin "1") (pinfunction "VCC_1") (pintype "bidirectional"))
      (node (ref "U2") (pin "1") (pinfunction "VCC_1") (pintype "bidirectional"))
      (node (ref "U3") (pin "1") (pinfunction "VCC_1") (pintype "bidirectional"))
      (node (ref "U5") (pin "1") (pinfunction "VCC_1") (pintype "bidirectional"))
      (node (ref "U7") (pin "36") (pinfunction "3V3(OUT)_36") (pintype "power_in"))
    )
    (net (code "2") (name "BOOTSEL") (class "Default")
      (node (ref "R16") (pin "1") (pinfunction "1_1") (pintype "passive"))
      (node (ref "U7") (pin "BOOTSEL") (pinfunction "BOOTSEL_BOOTSEL") (pintype "bidirectional"))
    )
    (net (code "3") (name "DMAN_RX_1") (class "Default")
      (node (ref "R24") (pin "1") (pinfunction "1_1") (pintype "passive"))
      (node (ref "U3") (pin "2") (pinfunction "R_2") (pintype "bidirectional"))
    )
    (net (code "4") (name "DMAN_RX_2") (class "Default")
      (node (ref "R25") (pin "1") (pinfunction "1_1") (pintype "passive"))
      (node (ref "U1") (pin "2") (pinfunction "R_2") (pintype "bidirectional"))
    )
    (net (code "5") (name "DMAN_RX_3") (class "Default")
      (node (ref "R26") (pin "1") (pinfunction "1_1") (pintype "passive"))
      (node (ref "U2") (pin "2") (pinfunction "R_2") (pintype "bidirectional"))
    )
    (net (code "6") (name "DMAN_RX_4") (class "Default")
      (node (ref "R20") (pin "1") (pinfunction "1_1") (pintype "passive"))
      (node (ref "U5") (pin "2") (pinfunction "R_2") (pintype "bidirectional"))
    )
    (net (code "7") (name "DMAN_TX_1") (class "Default")
      (node (ref "R23") (pin "1") (pinfunction "1_1") (pintype "passive"))
      (node (ref "U3") (pin "3") (pinfunction "D_3") (pintype "bidirectional"))
    )
    (net (code "8") (name "DMAN_TX_2") (class "Default")
      (node (ref "R22") (pin "1") (pinfunction "1_1") (pintype "passive"))
      (node (ref "U1") (pin "3") (pinfunction "D_3") (pintype "bidirectional"))
    )
    (net (code "9") (name "DMAN_TX_3") (class "Default")
      (node (ref "R21") (pin "1") (pinfunction "1_1") (pintype "passive"))
      (node (ref "U2") (pin "3") (pinfunction "D_3") (pintype "bidirectional"))
    )
    (net (code "10") (name "DMAN_TX_4") (class "Default")
      (node (ref "R17") (pin "1") (pinfunction "1_1") (pintype "passive"))
      (node (ref "U5") (pin "3") (pinfunction "D_3") (pintype "bidirectional"))
    )
    (net (code "11") (name "DNVT_1_SWITCH_RX_GREEN") (class "Default")
      (node (ref "GDT2") (pin "L2") (pinfunction "L2_L2") (pintype "bidirectional"))
      (node (ref "J1") (pin "6") (pinfunction "6_6") (pintype "bidirectional"))
      (node (ref "L4") (pin "2") (pinfunction "P$2_2") (pintype "bidirectional"))
    )
    (net (code "12") (name "DNVT_1_SWITCH_RX_GREEN-WHITE") (class "Default")
      (node (ref "GDT2") (pin "L1") (pinfunction "L1_L1") (pintype "bidirectional"))
      (node (ref "J1") (pin "3") (pinfunction "3_3") (pintype "bidirectional"))
      (node (ref "L3") (pin "2") (pinfunction "P$2_2") (pintype "bidirectional"))
    )
    (net (code "13") (name "DNVT_1_SWITCH_TX_BLUE") (class "Default")
      (node (ref "GDT1") (pin "L2") (pinfunction "L2_L2") (pintype "bidirectional"))
      (node (ref "J1") (pin "4") (pinfunction "4_4") (pintype "bidirectional"))
      (node (ref "L2") (pin "2") (pinfunction "P$2_2") (pintype "bidirectional"))
    )
    (net (code "14") (name "DNVT_1_SWITCH_TX_BLUE-WHITE") (class "Default")
      (node (ref "GDT1") (pin "L1") (pinfunction "L1_L1") (pintype "bidirectional"))
      (node (ref "J1") (pin "5") (pinfunction "5_5") (pintype "bidirectional"))
      (node (ref "L1") (pin "2") (pinfunction "P$2_2") (pintype "bidirectional"))
    )
    (net (code "15") (name "DNVT_2_SWITCH_RX_BROWN") (class "Default")
      (node (ref "GDT4") (pin "L1") (pinfunction "L1_L1") (pintype "bidirectional"))
      (node (ref "J1") (pin "8") (pinfunction "8_8") (pintype "bidirectional"))
      (node (ref "L7") (pin "2") (pinfunction "P$2_2") (pintype "bidirectional"))
    )
    (net (code "16") (name "DNVT_2_SWITCH_RX_BROWN-WHITE") (class "Default")
      (node (ref "GDT4") (pin "L2") (pinfunction "L2_L2") (pintype "bidirectional"))
      (node (ref "J1") (pin "7") (pinfunction "7_7") (pintype "bidirectional"))
      (node (ref "L8") (pin "2") (pinfunction "P$2_2") (pintype "bidirectional"))
    )
    (net (code "17") (name "DNVT_2_SWITCH_TX_ORANGE") (class "Default")
      (node (ref "GDT3") (pin "L2") (pinfunction "L2_L2") (pintype "bidirectional"))
      (node (ref "J1") (pin "2") (pinfunction "2_2") (pintype "bidirectional"))
      (node (ref "L6") (pin "2") (pinfunction "P$2_2") (pintype "bidirectional"))
    )
    (net (code "18") (name "DNVT_2_SWITCH_TX_ORANGE-WHITE") (class "Default")
      (node (ref "GDT3") (pin "L1") (pinfunction "L1_L1") (pintype "bidirectional"))
      (node (ref "J1") (pin "1") (pinfunction "1_1") (pintype "bidirectional"))
      (node (ref "L5") (pin "2") (pinfunction "P$2_2") (pintype "bidirectional"))
    )
    (net (code "19") (name "DNVT_3_SWITCH_RX_GREEN") (class "Default")
      (node (ref "GDT6") (pin "L2") (pinfunction "L2_L2") (pintype "bidirectional"))
      (node (ref "J2") (pin "6") (pinfunction "6_6") (pintype "bidirectional"))
      (node (ref "L12") (pin "2") (pinfunction "P$2_2") (pintype "bidirectional"))
    )
    (net (code "20") (name "DNVT_3_SWITCH_RX_GREEN-WHITE") (class "Default")
      (node (ref "GDT6") (pin "L1") (pinfunction "L1_L1") (pintype "bidirectional"))
      (node (ref "J2") (pin "3") (pinfunction "3_3") (pintype "bidirectional"))
      (node (ref "L11") (pin "2") (pinfunction "P$2_2") (pintype "bidirectional"))
    )
    (net (code "21") (name "DNVT_3_SWITCH_TX_BLUE") (class "Default")
      (node (ref "GDT5") (pin "L2") (pinfunction "L2_L2") (pintype "bidirectional"))
      (node (ref "J2") (pin "4") (pinfunction "4_4") (pintype "bidirectional"))
      (node (ref "L10") (pin "2") (pinfunction "P$2_2") (pintype "bidirectional"))
    )
    (net (code "22") (name "DNVT_3_SWITCH_TX_BLUE-WHITE") (class "Default")
      (node (ref "GDT5") (pin "L1") (pinfunction "L1_L1") (pintype "bidirectional"))
      (node (ref "J2") (pin "5") (pinfunction "5_5") (pintype "bidirectional"))
      (node (ref "L9") (pin "2") (pinfunction "P$2_2") (pintype "bidirectional"))
    )
    (net (code "23") (name "DNVT_4_SWITCH_RX_BROWN") (class "Default")
      (node (ref "GDT8") (pin "L1") (pinfunction "L1_L1") (pintype "bidirectional"))
      (node (ref "J2") (pin "8") (pinfunction "8_8") (pintype "bidirectional"))
      (node (ref "L15") (pin "2") (pinfunction "P$2_2") (pintype "bidirectional"))
    )
    (net (code "24") (name "DNVT_4_SWITCH_RX_BROWN-WHITE") (class "Default")
      (node (ref "GDT8") (pin "L2") (pinfunction "L2_L2") (pintype "bidirectional"))
      (node (ref "J2") (pin "7") (pinfunction "7_7") (pintype "bidirectional"))
      (node (ref "L16") (pin "2") (pinfunction "P$2_2") (pintype "bidirectional"))
    )
    (net (code "25") (name "DNVT_4_SWITCH_TX_ORANGE") (class "Default")
      (node (ref "GDT7") (pin "L2") (pinfunction "L2_L2") (pintype "bidirectional"))
      (node (ref "J2") (pin "2") (pinfunction "2_2") (pintype "bidirectional"))
      (node (ref "L14") (pin "2") (pinfunction "P$2_2") (pintype "bidirectional"))
    )
    (net (code "26") (name "DNVT_4_SWITCH_TX_ORANGE-WHITE") (class "Default")
      (node (ref "GDT7") (pin "L1") (pinfunction "L1_L1") (pintype "bidirectional"))
      (node (ref "J2") (pin "1") (pinfunction "1_1") (pintype "bidirectional"))
      (node (ref "L13") (pin "2") (pinfunction "P$2_2") (pintype "bidirectional"))
    )
    (net (code "27") (name "GND") (class "Default")
      (node (ref "C1") (pin "2") (pinfunction "2_2") (pintype "passive"))
      (node (ref "C11") (pin "2") (pinfunction "2_2") (pintype "passive"))
      (node (ref "C12") (pin "2") (pinfunction "2_2") (pintype "passive"))
      (node (ref "C13") (pin "2") (pinfunction "2_2") (pintype "passive"))
      (node (ref "C14") (pin "2") (pinfunction "2_2") (pintype "passive"))
      (node (ref "C15") (pin "2") (pinfunction "2_2") (pintype "passive"))
      (node (ref "C16") (pin "1") (pinfunction "1_1") (pintype "passive"))
      (node (ref "C17") (pin "2") (pinfunction "2_2") (pintype "passive"))
      (node (ref "C24") (pin "2") (pinfunction "2_2") (pintype "passive"))
      (node (ref "C31") (pin "2") (pinfunction "2_2") (pintype "passive"))
      (node (ref "C38") (pin "1") (pinfunction "1_1") (pintype "passive"))
      (node (ref "C39") (pin "1") (pinfunction "1_1") (pintype "passive"))
      (node (ref "C41") (pin "2") (pinfunction "2_2") (pintype "passive"))
      (node (ref "C42") (pin "2") (pinfunction "2_2") (pintype "passive"))
      (node (ref "C5") (pin "2") (pinfunction "2_2") (pintype "passive"))
      (node (ref "C6") (pin "2") (pinfunction "2_2") (pintype "passive"))
      (node (ref "C9") (pin "2") (pinfunction "2_2") (pintype "passive"))
      (node (ref "J5") (pin "C1") (pinfunction "VSS_C1") (pintype "bidirectional"))
      (node (ref "J5") (pin "C2") (pinfunction "VSS_C2") (pintype "bidirectional"))
      (node (ref "J5") (pin "C3") (pinfunction "VSS_C3") (pintype "bidirectional"))
      (node (ref "J5") (pin "C4") (pinfunction "VSS_C4") (pintype "bidirectional"))
      (node (ref "J5") (pin "DSW2") (pinfunction "SW2_DSW2") (pintype "bidirectional"))
      (node (ref "J5") (pin "P6") (pinfunction "VSS_P6") (pintype "bidirectional"))
      (node (ref "JP1") (pin "6") (pinfunction "6_6") (pintype "passive"))
      (node (ref "JP3") (pin "1") (pinfunction "1_1") (pintype "passive"))
      (node (ref "R19") (pin "1") (pinfunction "1_1") (pintype "passive"))
      (node (ref "R28") (pin "2") (pinfunction "2_2") (pintype "passive"))
      (node (ref "R31") (pin "2") (pinfunction "2_2") (pintype "passive"))
      (node (ref "R8") (pin "1") (pinfunction "1_1") (pintype "passive"))
      (node (ref "SW1") (pin "S1") (pinfunction "1_S1") (pintype "passive"))
      (node (ref "SW2") (pin "1") (pinfunction "1_1") (pintype "passive"))
      (node (ref "SW2") (pin "2") (pinfunction "2_2") (pintype "passive"))
      (node (ref "SW2") (pin "3") (pinfunction "3_3") (pintype "passive"))
      (node (ref "SW2") (pin "4") (pinfunction "4_4") (pintype "passive"))
      (node (ref "U1") (pin "4") (pinfunction "GND_4") (pintype "bidirectional"))
      (node (ref "U2") (pin "4") (pinfunction "GND_4") (pintype "bidirectional"))
      (node (ref "U3") (pin "4") (pinfunction "GND_4") (pintype "bidirectional"))
      (node (ref "U5") (pin "4") (pinfunction "GND_4") (pintype "bidirectional"))
      (node (ref "U7") (pin "13") (pinfunction "GND_13") (pintype "power_in"))
      (node (ref "U7") (pin "18") (pinfunction "GND_18") (pintype "power_in"))
      (node (ref "U7") (pin "23") (pinfunction "GND_23") (pintype "power_in"))
      (node (ref "U7") (pin "28") (pinfunction "GND_28") (pintype "power_in"))
      (node (ref "U7") (pin "3") (pinfunction "GND_3") (pintype "power_in"))
      (node (ref "U7") (pin "33") (pinfunction "GND_33") (pintype "power_in"))
      (node (ref "U7") (pin "38") (pinfunction "GND_38") (pintype "power_in"))
      (node (ref "U7") (pin "8") (pinfunction "GND_8") (pintype "power_in"))
    )
    (net (code "28") (name "GP0_SD_MISO") (class "Default")
      (node (ref "R10") (pin "2") (pinfunction "2_2") (pintype "passive"))
      (node (ref "U7") (pin "1") (pinfunction "GP0_1") (pintype "bidirectional"))
    )
    (net (code "29") (name "GP1_SD_SS") (class "Default")
      (node (ref "R1") (pin "2") (pinfunction "2_2") (pintype "passive"))
      (node (ref "U7") (pin "2") (pinfunction "GP1_2") (pintype "bidirectional"))
    )
    (net (code "30") (name "GP2_SD_CLK") (class "Default")
      (node (ref "R4") (pin "2") (pinfunction "2_2") (pintype "passive"))
      (node (ref "U7") (pin "4") (pinfunction "GP2_4") (pintype "bidirectional"))
    )
    (net (code "31") (name "GP3_SD_MOSI") (class "Default")
      (node (ref "R2") (pin "2") (pinfunction "2_2") (pintype "passive"))
      (node (ref "U7") (pin "5") (pinfunction "GP3_5") (pintype "bidirectional"))
    )
    (net (code "32") (name "GP4_REBOOT") (class "Default")
      (node (ref "R27") (pin "1") (pinfunction "1_1") (pintype "passive"))
      (node (ref "U7") (pin "6") (pinfunction "GP4_6") (pintype "bidirectional"))
    )
    (net (code "33") (name "GP5_SD_DET") (class "Default")
      (node (ref "J5") (pin "DSW1") (pinfunction "SW1_DSW1") (pintype "bidirectional"))
      (node (ref "R3") (pin "2") (pinfunction "2_2") (pintype "passive"))
      (node (ref "U7") (pin "7") (pinfunction "GP5_7") (pintype "bidirectional"))
    )
    (net (code "34") (name "GP6_OLED_SDA") (class "Default")
      (node (ref "JP3") (pin "4") (pinfunction "4_4") (pintype "passive"))
      (node (ref "R15") (pin "2") (pinfunction "2_2") (pintype "passive"))
      (node (ref "U7") (pin "9") (pinfunction "GP6_9") (pintype "bidirectional"))
    )
    (net (code "35") (name "GP7_OLED_SCL") (class "Default")
      (node (ref "JP3") (pin "3") (pinfunction "3_3") (pintype "passive"))
      (node (ref "R9") (pin "2") (pinfunction "2_2") (pintype "passive"))
      (node (ref "U7") (pin "10") (pinfunction "GP7_10") (pintype "bidirectional"))
    )
    (net (code "36") (name "GP8_REVISION_1") (class "Default")
      (node (ref "R31") (pin "1") (pinfunction "1_1") (pintype "passive"))
      (node (ref "R35") (pin "2") (pinfunction "2_2") (pintype "passive"))
      (node (ref "U7") (pin "11") (pinfunction "GP8_11") (pintype "bidirectional"))
    )
    (net (code "37") (name "GP9") (class "Default")
      (node (ref "JP1") (pin "2") (pinfunction "2_2") (pintype "passive"))
      (node (ref "U7") (pin "12") (pinfunction "GP9_12") (pintype "bidirectional"))
    )
    (net (code "38") (name "GP10") (class "Default")
      (node (ref "JP1") (pin "1") (pinfunction "1_1") (pintype "passive"))
      (node (ref "U7") (pin "14") (pinfunction "GP10_14") (pintype "bidirectional"))
    )
    (net (code "39") (name "GP11") (class "Default")
      (node (ref "JP1") (pin "4") (pinfunction "4_4") (pintype "passive"))
      (node (ref "U7") (pin "15") (pinfunction "GP11_15") (pintype "bidirectional"))
    )
    (net (code "40") (name "GP12") (class "Default")
      (node (ref "JP1") (pin "3") (pinfunction "3_3") (pintype "passive"))
      (node (ref "U7") (pin "16") (pinfunction "GP12_16") (pintype "bidirectional"))
    )
    (net (code "41") (name "GP13") (class "Default")
      (node (ref "SW2") (pin "7") (pinfunction "7_7") (pintype "passive"))
      (node (ref "U7") (pin "17") (pinfunction "GP13_17") (pintype "bidirectional"))
    )
    (net (code "42") (name "GP14") (class "Default")
      (node (ref "SW2") (pin "6") (pinfunction "6_6") (pintype "passive"))
      (node (ref "U7") (pin "19") (pinfunction "GP14_19") (pintype "bidirectional"))
    )
    (net (code "43") (name "GP15") (class "Default")
      (node (ref "SW2") (pin "5") (pinfunction "5_5") (pintype "passive"))
      (node (ref "U7") (pin "20") (pinfunction "GP15_20") (pintype "bidirectional"))
    )
    (net (code "44") (name "GP22_REVISION_2") (class "Default")
      (node (ref "R28") (pin "1") (pinfunction "1_1") (pintype "passive"))
      (node (ref "R30") (pin "2") (pinfunction "2_2") (pintype "passive"))
      (node (ref "U7") (pin "29") (pinfunction "GP22_29") (pintype "bidirectional"))
    )
    (net (code "45") (name "GP28") (class "Default")
      (node (ref "SW2") (pin "8") (pinfunction "8_8") (pintype "passive"))
      (node (ref "U7") (pin "34") (pinfunction "GP28_34") (pintype "bidirectional"))
    )
    (net (code "46") (name "Net-(C8-Pad1)") (class "Default")
      (node (ref "C8") (pin "1") (pinfunction "1_1") (pintype "passive"))
      (node (ref "R11") (pin "2") (pinfunction "2_2") (pintype "passive"))
      (node (ref "R12") (pin "2") (pinfunction "2_2") (pintype "passive"))
      (node (ref "T1") (pin "6") (pinfunction "6_6") (pintype "bidirectional"))
    )
    (net (code "47") (name "Net-(C8-Pad2)") (class "Default")
      (node (ref "C8") (pin "2") (pinfunction "2_2") (pintype "passive"))
      (node (ref "R11") (pin "1") (pinfunction "1_1") (pintype "passive"))
      (node (ref "R13") (pin "2") (pinfunction "2_2") (pintype "passive"))
      (node (ref "T1") (pin "4") (pinfunction "4_4") (pintype "bidirectional"))
    )
    (net (code "48") (name "Net-(C23-Pad1)") (class "Default")
      (node (ref "C23") (pin "1") (pinfunction "1_1") (pintype "passive"))
      (node (ref "R36") (pin "2") (pinfunction "2_2") (pintype "passive"))
      (node (ref "R37") (pin "2") (pinfunction "2_2") (pintype "passive"))
      (node (ref "T3") (pin "6") (pinfunction "6_6") (pintype "bidirectional"))
    )
    (net (code "49") (name "Net-(C23-Pad2)") (class "Default")
      (node (ref "C23") (pin "2") (pinfunction "2_2") (pintype "passive"))
      (node (ref "R36") (pin "1") (pinfunction "1_1") (pintype "passive"))
      (node (ref "R38") (pin "2") (pinfunction "2_2") (pintype "passive"))
      (node (ref "T3") (pin "4") (pinfunction "4_4") (pintype "bidirectional"))
    )
    (net (code "50") (name "Net-(C30-Pad1)") (class "Default")
      (node (ref "C30") (pin "1") (pinfunction "1_1") (pintype "passive"))
      (node (ref "R46") (pin "2") (pinfunction "2_2") (pintype "passive"))
      (node (ref "R47") (pin "2") (pinfunction "2_2") (pintype "passive"))
      (node (ref "T7") (pin "6") (pinfunction "6_6") (pintype "bidirectional"))
    )
    (net (code "51") (name "Net-(C30-Pad2)") (class "Default")
      (node (ref "C30") (pin "2") (pinfunction "2_2") (pintype "passive"))
      (node (ref "R46") (pin "1") (pinfunction "1_1") (pintype "passive"))
      (node (ref "R48") (pin "2") (pinfunction "2_2") (pintype "passive"))
      (node (ref "T7") (pin "4") (pinfunction "4_4") (pintype "bidirectional"))
    )
    (net (code "52") (name "Net-(C37-Pad1)") (class "Default")
      (node (ref "C37") (pin "1") (pinfunction "1_1") (pintype "passive"))
      (node (ref "R56") (pin "2") (pinfunction "2_2") (pintype "passive"))
      (node (ref "R57") (pin "2") (pinfunction "2_2") (pintype "passive"))
      (node (ref "T5") (pin "6") (pinfunction "6_6") (pintype "bidirectional"))
    )
    (net (code "53") (name "Net-(C37-Pad2)") (class "Default")
      (node (ref "C37") (pin "2") (pinfunction "2_2") (pintype "passive"))
      (node (ref "R56") (pin "1") (pinfunction "1_1") (pintype "passive"))
      (node (ref "R58") (pin "2") (pinfunction "2_2") (pintype "passive"))
      (node (ref "T5") (pin "4") (pinfunction "4_4") (pintype "bidirectional"))
    )
    (net (code "54") (name "Net-(C40-Pad1)") (class "Default")
      (node (ref "C40") (pin "1") (pinfunction "1_1") (pintype "passive"))
      (node (ref "R29") (pin "1") (pinfunction "1_1") (pintype "passive"))
    )
    (net (code "55") (name "Net-(D3-K)") (class "Default")
      (node (ref "C10") (pin "1") (pinfunction "1_1") (pintype "passive"))
      (node (ref "D3") (pin "C") (pinfunction "K_C") (pintype "bidirectional"))
      (node (ref "L1") (pin "1") (pinfunction "P$1_1") (pintype "bidirectional"))
      (node (ref "R5") (pin "2") (pinfunction "2_2") (pintype "passive"))
      (node (ref "T1") (pin "1") (pinfunction "1_1") (pintype "bidirectional"))
    )
    (net (code "56") (name "Net-(D4-K)") (class "Default")
      (node (ref "C4") (pin "1") (pinfunction "1_1") (pintype "passive"))
      (node (ref "D4") (pin "C") (pinfunction "K_C") (pintype "bidirectional"))
      (node (ref "L3") (pin "1") (pinfunction "P$1_1") (pintype "bidirectional"))
      (node (ref "R6") (pin "2") (pinfunction "2_2") (pintype "passive"))
      (node (ref "T2") (pin "1") (pinfunction "1_1") (pintype "bidirectional"))
    )
    (net (code "57") (name "Net-(D8-K)") (class "Default")
      (node (ref "C18") (pin "1") (pinfunction "1_1") (pintype "passive"))
      (node (ref "D8") (pin "C") (pinfunction "K_C") (pintype "bidirectional"))
      (node (ref "L5") (pin "1") (pinfunction "P$1_1") (pintype "bidirectional"))
      (node (ref "R32") (pin "2") (pinfunction "2_2") (pintype "passive"))
      (node (ref "T3") (pin "1") (pinfunction "1_1") (pintype "bidirectional"))
    )
    (net (code "58") (name "Net-(D9-K)") (class "Default")
      (node (ref "C21") (pin "1") (pinfunction "1_1") (pintype "passive"))
      (node (ref "D9") (pin "C") (pinfunction "K_C") (pintype "bidirectional"))
      (node (ref "L7") (pin "1") (pinfunction "P$1_1") (pintype "bidirectional"))
      (node (ref "R33") (pin "2") (pinfunction "2_2") (pintype "passive"))
      (node (ref "T4") (pin "1") (pinfunction "1_1") (pintype "bidirectional"))
    )
    (net (code "59") (name "Net-(D10-K)") (class "Default")
      (node (ref "C25") (pin "1") (pinfunction "1_1") (pintype "passive"))
      (node (ref "D10") (pin "C") (pinfunction "K_C") (pintype "bidirectional"))
      (node (ref "L13") (pin "1") (pinfunction "P$1_1") (pintype "bidirectional"))
      (node (ref "R42") (pin "2") (pinfunction "2_2") (pintype "passive"))
      (node (ref "T7") (pin "1") (pinfunction "1_1") (pintype "bidirectional"))
    )
    (net (code "60") (name "Net-(D11-K)") (class "Default")
      (node (ref "C28") (pin "1") (pinfunction "1_1") (pintype "passive"))
      (node (ref "D11") (pin "C") (pinfunction "K_C") (pintype "bidirectional"))
      (node (ref "L15") (pin "1") (pinfunction "P$1_1") (pintype "bidirectional"))
      (node (ref "R43") (pin "2") (pinfunction "2_2") (pintype "passive"))
      (node (ref "T8") (pin "1") (pinfunction "1_1") (pintype "bidirectional"))
    )
    (net (code "61") (name "Net-(D12-K)") (class "Default")
      (node (ref "C32") (pin "1") (pinfunction "1_1") (pintype "passive"))
      (node (ref "D12") (pin "C") (pinfunction "K_C") (pintype "bidirectional"))
      (node (ref "L9") (pin "1") (pinfunction "P$1_1") (pintype "bidirectional"))
      (node (ref "R52") (pin "2") (pinfunction "2_2") (pintype "passive"))
      (node (ref "T5") (pin "1") (pinfunction "1_1") (pintype "bidirectional"))
    )
    (net (code "62") (name "Net-(D13-K)") (class "Default")
      (node (ref "C35") (pin "1") (pinfunction "1_1") (pintype "passive"))
      (node (ref "D13") (pin "C") (pinfunction "K_C") (pintype "bidirectional"))
      (node (ref "L11") (pin "1") (pinfunction "P$1_1") (pintype "bidirectional"))
      (node (ref "R53") (pin "2") (pinfunction "2_2") (pintype "passive"))
      (node (ref "T6") (pin "1") (pinfunction "1_1") (pintype "bidirectional"))
    )
    (net (code "63") (name "Net-(F1-P$1)") (class "Default")
      (node (ref "F1") (pin "1") (pinfunction "P$1_1") (pintype "bidirectional"))
      (node (ref "T1") (pin "2") (pinfunction "2_2") (pintype "bidirectional"))
    )
    (net (code "64") (name "Net-(F2-P$1)") (class "Default")
      (node (ref "F2") (pin "1") (pinfunction "P$1_1") (pintype "bidirectional"))
      (node (ref "T3") (pin "2") (pinfunction "2_2") (pintype "bidirectional"))
    )
    (net (code "65") (name "Net-(F3-P$1)") (class "Default")
      (node (ref "F3") (pin "1") (pinfunction "P$1_1") (pintype "bidirectional"))
      (node (ref "T5") (pin "2") (pinfunction "2_2") (pintype "bidirectional"))
    )
    (net (code "66") (name "Net-(F4-P$1)") (class "Default")
      (node (ref "F4") (pin "1") (pinfunction "P$1_1") (pintype "bidirectional"))
      (node (ref "T7") (pin "2") (pinfunction "2_2") (pintype "bidirectional"))
    )
    (net (code "67") (name "Net-(J4-V+)") (class "Default")
      (node (ref "CR1") (pin "A") (pinfunction "A_A") (pintype "bidirectional"))
      (node (ref "CR2") (pin "K") (pinfunction "K_K") (pintype "bidirectional"))
      (node (ref "J4") (pin "1") (pinfunction "V+_1") (pintype "bidirectional"))
    )
    (net (code "68") (name "Net-(J5-CLK)") (class "Default")
      (node (ref "J5") (pin "P5") (pinfunction "CLK_P5") (pintype "bidirectional"))
      (node (ref "R4") (pin "1") (pinfunction "1_1") (pintype "passive"))
    )
    (net (code "69") (name "Net-(J5-CMD{slash}MOSI)") (class "Default")
      (node (ref "J5") (pin "P3") (pinfunction "CMD/MOSI_P3") (pintype "bidirectional"))
      (node (ref "R2") (pin "1") (pinfunction "1_1") (pintype "passive"))
    )
    (net (code "70") (name "Net-(J5-DAT0{slash}MISO)") (class "Default")
      (node (ref "J5") (pin "P7") (pinfunction "DAT0/MISO_P7") (pintype "bidirectional"))
      (node (ref "R10") (pin "1") (pinfunction "1_1") (pintype "passive"))
    )
    (net (code "71") (name "Net-(J5-DAT3{slash}CS)") (class "Default")
      (node (ref "J5") (pin "P2") (pinfunction "DAT3/CS_P2") (pintype "bidirectional"))
      (node (ref "R1") (pin "1") (pinfunction "1_1") (pintype "passive"))
    )
    (net (code "72") (name "Net-(L2-P$1)") (class "Default")
      (node (ref "C2") (pin "2") (pinfunction "2_2") (pintype "passive"))
      (node (ref "D3") (pin "A") (pinfunction "A_A") (pintype "bidirectional"))
      (node (ref "L2") (pin "1") (pinfunction "P$1_1") (pintype "bidirectional"))
      (node (ref "R5") (pin "1") (pinfunction "1_1") (pintype "passive"))
      (node (ref "T1") (pin "3") (pinfunction "3_3") (pintype "bidirectional"))
    )
    (net (code "73") (name "Net-(L4-P$1)") (class "Default")
      (node (ref "C3") (pin "2") (pinfunction "2_2") (pintype "passive"))
      (node (ref "D4") (pin "A") (pinfunction "A_A") (pintype "bidirectional"))
      (node (ref "L4") (pin "1") (pinfunction "P$1_1") (pintype "bidirectional"))
      (node (ref "R6") (pin "1") (pinfunction "1_1") (pintype "passive"))
      (node (ref "T2") (pin "3") (pinfunction "3_3") (pintype "bidirectional"))
    )
    (net (code "74") (name "Net-(L6-P$1)") (class "Default")
      (node (ref "C19") (pin "2") (pinfunction "2_2") (pintype "passive"))
      (node (ref "D8") (pin "A") (pinfunction "A_A") (pintype "bidirectional"))
      (node (ref "L6") (pin "1") (pinfunction "P$1_1") (pintype "bidirectional"))
      (node (ref "R32") (pin "1") (pinfunction "1_1") (pintype "passive"))
      (node (ref "T3") (pin "3") (pinfunction "3_3") (pintype "bidirectional"))
    )
    (net (code "75") (name "Net-(L8-P$1)") (class "Default")
      (node (ref "C20") (pin "2") (pinfunction "2_2") (pintype "passive"))
      (node (ref "D9") (pin "A") (pinfunction "A_A") (pintype "bidirectional"))
      (node (ref "L8") (pin "1") (pinfunction "P$1_1") (pintype "bidirectional"))
      (node (ref "R33") (pin "1") (pinfunction "1_1") (pintype "passive"))
      (node (ref "T4") (pin "3") (pinfunction "3_3") (pintype "bidirectional"))
    )
    (net (code "76") (name "Net-(L10-P$1)") (class "Default")
      (node (ref "C33") (pin "2") (pinfunction "2_2") (pintype "passive"))
      (node (ref "D12") (pin "A") (pinfunction "A_A") (pintype "bidirectional"))
      (node (ref "L10") (pin "1") (pinfunction "P$1_1") (pintype "bidirectional"))
      (node (ref "R52") (pin "1") (pinfunction "1_1") (pintype "passive"))
      (node (ref "T5") (pin "3") (pinfunction "3_3") (pintype "bidirectional"))
    )
    (net (code "77") (name "Net-(L12-P$1)") (class "Default")
      (node (ref "C34") (pin "2") (pinfunction "2_2") (pintype "passive"))
      (node (ref "D13") (pin "A") (pinfunction "A_A") (pintype "bidirectional"))
      (node (ref "L12") (pin "1") (pinfunction "P$1_1") (pintype "bidirectional"))
      (node (ref "R53") (pin "1") (pinfunction "1_1") (pintype "passive"))
      (node (ref "T6") (pin "3") (pinfunction "3_3") (pintype "bidirectional"))
    )
    (net (code "78") (name "Net-(L14-P$1)") (class "Default")
      (node (ref "C26") (pin "2") (pinfunction "2_2") (pintype "passive"))
      (node (ref "D10") (pin "A") (pinfunction "A_A") (pintype "bidirectional"))
      (node (ref "L14") (pin "1") (pinfunction "P$1_1") (pintype "bidirectional"))
      (node (ref "R42") (pin "1") (pinfunction "1_1") (pintype "passive"))
      (node (ref "T7") (pin "3") (pinfunction "3_3") (pintype "bidirectional"))
    )
    (net (code "79") (name "Net-(L16-P$1)") (class "Default")
      (node (ref "C27") (pin "2") (pinfunction "2_2") (pintype "passive"))
      (node (ref "D11") (pin "A") (pinfunction "A_A") (pintype "bidirectional"))
      (node (ref "L16") (pin "1") (pinfunction "P$1_1") (pintype "bidirectional"))
      (node (ref "R43") (pin "1") (pinfunction "1_1") (pintype "passive"))
      (node (ref "T8") (pin "3") (pinfunction "3_3") (pintype "bidirectional"))
    )
    (net (code "80") (name "Net-(R7-Pad2)") (class "Default")
      (node (ref "R7") (pin "2") (pinfunction "2_2") (pintype "passive"))
      (node (ref "T2") (pin "2") (pinfunction "2_2") (pintype "bidirectional"))
    )
    (net (code "81") (name "Net-(R34-Pad2)") (class "Default")
      (node (ref "R34") (pin "2") (pinfunction "2_2") (pintype "passive"))
      (node (ref "T4") (pin "2") (pinfunction "2_2") (pintype "bidirectional"))
    )
    (net (code "82") (name "Net-(R44-Pad2)") (class "Default")
      (node (ref "R44") (pin "2") (pinfunction "2_2") (pintype "passive"))
      (node (ref "T8") (pin "2") (pinfunction "2_2") (pintype "bidirectional"))
    )
    (net (code "83") (name "Net-(R54-Pad2)") (class "Default")
      (node (ref "R54") (pin "2") (pinfunction "2_2") (pintype "passive"))
      (node (ref "T6") (pin "2") (pinfunction "2_2") (pintype "bidirectional"))
    )
    (net (code "84") (name "Net-(SW1-2)") (class "Default")
      (node (ref "R16") (pin "2") (pinfunction "2_2") (pintype "passive"))
      (node (ref "R27") (pin "2") (pinfunction "2_2") (pintype "passive"))
      (node (ref "SW1") (pin "S2") (pinfunction "2_S2") (pintype "passive"))
    )
    (net (code "85") (name "Net-(U1-A)") (class "Default")
      (node (ref "C22") (pin "2") (pinfunction "2_2") (pintype "passive"))
      (node (ref "R41") (pin "1") (pinfunction "1_1") (pintype "passive"))
      (node (ref "T4") (pin "4") (pinfunction "4_4") (pintype "bidirectional"))
      (node (ref "U1") (pin "8") (pinfunction "A_8") (pintype "bidirectional"))
    )
    (net (code "86") (name "Net-(U1-B)") (class "Default")
      (node (ref "C22") (pin "1") (pinfunction "1_1") (pintype "passive"))
      (node (ref "R41") (pin "2") (pinfunction "2_2") (pintype "passive"))
      (node (ref "T4") (pin "6") (pinfunction "6_6") (pintype "bidirectional"))
      (node (ref "U1") (pin "7") (pinfunction "B_7") (pintype "bidirectional"))
    )
    (net (code "87") (name "Net-(U1-Y)") (class "Default")
      (node (ref "R37") (pin "1") (pinfunction "1_1") (pintype "passive"))
      (node (ref "U1") (pin "5") (pinfunction "Y_5") (pintype "bidirectional"))
    )
    (net (code "88") (name "Net-(U1-Z)") (class "Default")
      (node (ref "R38") (pin "1") (pinfunction "1_1") (pintype "passive"))
      (node (ref "U1") (pin "6") (pinfunction "Z_6") (pintype "bidirectional"))
    )
    (net (code "89") (name "Net-(U2-A)") (class "Default")
      (node (ref "C36") (pin "2") (pinfunction "2_2") (pintype "passive"))
      (node (ref "R61") (pin "1") (pinfunction "1_1") (pintype "passive"))
      (node (ref "T6") (pin "4") (pinfunction "4_4") (pintype "bidirectional"))
      (node (ref "U2") (pin "8") (pinfunction "A_8") (pintype "bidirectional"))
    )
    (net (code "90") (name "Net-(U2-B)") (class "Default")
      (node (ref "C36") (pin "1") (pinfunction "1_1") (pintype "passive"))
      (node (ref "R61") (pin "2") (pinfunction "2_2") (pintype "passive"))
      (node (ref "T6") (pin "6") (pinfunction "6_6") (pintype "bidirectional"))
      (node (ref "U2") (pin "7") (pinfunction "B_7") (pintype "bidirectional"))
    )
    (net (code "91") (name "Net-(U2-Y)") (class "Default")
      (node (ref "R57") (pin "1") (pinfunction "1_1") (pintype "passive"))
      (node (ref "U2") (pin "5") (pinfunction "Y_5") (pintype "bidirectional"))
    )
    (net (code "92") (name "Net-(U2-Z)") (class "Default")
      (node (ref "R58") (pin "1") (pinfunction "1_1") (pintype "passive"))
      (node (ref "U2") (pin "6") (pinfunction "Z_6") (pintype "bidirectional"))
    )
    (net (code "93") (name "Net-(U3-A)") (class "Default")
      (node (ref "C7") (pin "2") (pinfunction "2_2") (pintype "passive"))
      (node (ref "R14") (pin "1") (pinfunction "1_1") (pintype "passive"))
      (node (ref "T2") (pin "4") (pinfunction "4_4") (pintype "bidirectional"))
      (node (ref "U3") (pin "8") (pinfunction "A_8") (pintype "bidirectional"))
    )
    (net (code "94") (name "Net-(U3-B)") (class "Default")
      (node (ref "C7") (pin "1") (pinfunction "1_1") (pintype "passive"))
      (node (ref "R14") (pin "2") (pinfunction "2_2") (pintype "passive"))
      (node (ref "T2") (pin "6") (pinfunction "6_6") (pintype "bidirectional"))
      (node (ref "U3") (pin "7") (pinfunction "B_7") (pintype "bidirectional"))
    )
    (net (code "95") (name "Net-(U3-Y)") (class "Default")
      (node (ref "R12") (pin "1") (pinfunction "1_1") (pintype "passive"))
      (node (ref "U3") (pin "5") (pinfunction "Y_5") (pintype "bidirectional"))
    )
    (net (code "96") (name "Net-(U3-Z)") (class "Default")
      (node (ref "R13") (pin "1") (pinfunction "1_1") (pintype "passive"))
      (node (ref "U3") (pin "6") (pinfunction "Z_6") (pintype "bidirectional"))
    )
    (net (code "97") (name "Net-(U5-A)") (class "Default")
      (node (ref "C29") (pin "2") (pinfunction "2_2") (pintype "passive"))
      (node (ref "R51") (pin "1") (pinfunction "1_1") (pintype "passive"))
      (node (ref "T8") (pin "4") (pinfunction "4_4") (pintype "bidirectional"))
      (node (ref "U5") (pin "8") (pinfunction "A_8") (pintype "bidirectional"))
    )
    (net (code "98") (name "Net-(U5-B)") (class "Default")
      (node (ref "C29") (pin "1") (pinfunction "1_1") (pintype "passive"))
      (node (ref "R51") (pin "2") (pinfunction "2_2") (pintype "passive"))
      (node (ref "T8") (pin "6") (pinfunction "6_6") (pintype "bidirectional"))
      (node (ref "U5") (pin "7") (pinfunction "B_7") (pintype "bidirectional"))
    )
    (net (code "99") (name "Net-(U5-Y)") (class "Default")
      (node (ref "R47") (pin "1") (pinfunction "1_1") (pintype "passive"))
      (node (ref "U5") (pin "5") (pinfunction "Y_5") (pintype "bidirectional"))
    )
    (net (code "100") (name "Net-(U5-Z)") (class "Default")
      (node (ref "R48") (pin "1") (pinfunction "1_1") (pintype "passive"))
      (node (ref "U5") (pin "6") (pinfunction "Z_6") (pintype "bidirectional"))
    )
    (net (code "101") (name "Net-(U7-GP16)") (class "Default")
      (node (ref "R24") (pin "2") (pinfunction "2_2") (pintype "passive"))
      (node (ref "U7") (pin "21") (pinfunction "GP16_21") (pintype "bidirectional"))
    )
    (net (code "102") (name "Net-(U7-GP17)") (class "Default")
      (node (ref "R23") (pin "2") (pinfunction "2_2") (pintype "passive"))
      (node (ref "U7") (pin "22") (pinfunction "GP17_22") (pintype "bidirectional"))
    )
    (net (code "103") (name "Net-(U7-GP18)") (class "Default")
      (node (ref "R25") (pin "2") (pinfunction "2_2") (pintype "passive"))
      (node (ref "U7") (pin "24") (pinfunction "GP18_24") (pintype "bidirectional"))
    )
    (net (code "104") (name "Net-(U7-GP19)") (class "Default")
      (node (ref "R22") (pin "2") (pinfunction "2_2") (pintype "passive"))
      (node (ref "U7") (pin "25") (pinfunction "GP19_25") (pintype "bidirectional"))
    )
    (net (code "105") (name "Net-(U7-GP20)") (class "Default")
      (node (ref "R26") (pin "2") (pinfunction "2_2") (pintype "passive"))
      (node (ref "U7") (pin "26") (pinfunction "GP20_26") (pintype "bidirectional"))
    )
    (net (code "106") (name "Net-(U7-GP21)") (class "Default")
      (node (ref "R21") (pin "2") (pinfunction "2_2") (pintype "passive"))
      (node (ref "U7") (pin "27") (pinfunction "GP21_27") (pintype "bidirectional"))
    )
    (net (code "107") (name "Net-(U7-GP26)") (class "Default")
      (node (ref "R20") (pin "2") (pinfunction "2_2") (pintype "passive"))
      (node (ref "U7") (pin "31") (pinfunction "GP26_31") (pintype "bidirectional"))
    )
    (net (code "108") (name "Net-(U7-GP27)") (class "Default")
      (node (ref "R17") (pin "2") (pinfunction "2_2") (pintype "passive"))
      (node (ref "U7") (pin "32") (pinfunction "GP27_32") (pintype "bidirectional"))
    )
    (net (code "109") (name "PE") (class "Default")
      (node (ref "C10") (pin "2") (pinfunction "2_2") (pintype "passive"))
      (node (ref "C16") (pin "2") (pinfunction "2_2") (pintype "passive"))
      (node (ref "C18") (pin "2") (pinfunction "2_2") (pintype "passive"))
      (node (ref "C19") (pin "1") (pinfunction "1_1") (pintype "passive"))
      (node (ref "C2") (pin "1") (pinfunction "1_1") (pintype "passive"))
      (node (ref "C20") (pin "1") (pinfunction "1_1") (pintype "passive"))
      (node (ref "C21") (pin "2") (pinfunction "2_2") (pintype "passive"))
      (node (ref "C25") (pin "2") (pinfunction "2_2") (pintype "passive"))
      (node (ref "C26") (pin "1") (pinfunction "1_1") (pintype "passive"))
      (node (ref "C27") (pin "1") (pinfunction "1_1") (pintype "passive"))
      (node (ref "C28") (pin "2") (pinfunction "2_2") (pintype "passive"))
      (node (ref "C3") (pin "1") (pinfunction "1_1") (pintype "passive"))
      (node (ref "C32") (pin "2") (pinfunction "2_2") (pintype "passive"))
      (node (ref "C33") (pin "1") (pinfunction "1_1") (pintype "passive"))
      (node (ref "C34") (pin "1") (pinfunction "1_1") (pintype "passive"))
      (node (ref "C35") (pin "2") (pinfunction "2_2") (pintype "passive"))
      (node (ref "C38") (pin "2") (pinfunction "2_2") (pintype "passive"))
      (node (ref "C39") (pin "2") (pinfunction "2_2") (pintype "passive"))
      (node (ref "C4") (pin "2") (pinfunction "2_2") (pintype "passive"))
      (node (ref "C40") (pin "2") (pinfunction "2_2") (pintype "passive"))
      (node (ref "CR2") (pin "A") (pinfunction "A_A") (pintype "bidirectional"))
      (node (ref "GDT1") (pin "C") (pinfunction "C_C") (pintype "bidirectional"))
      (node (ref "GDT2") (pin "C") (pinfunction "C_C") (pintype "bidirectional"))
      (node (ref "GDT3") (pin "C") (pinfunction "C_C") (pintype "bidirectional"))
      (node (ref "GDT4") (pin "C") (pinfunction "C_C") (pintype "bidirectional"))
      (node (ref "GDT5") (pin "C") (pinfunction "C_C") (pintype "bidirectional"))
      (node (ref "GDT6") (pin "C") (pinfunction "C_C") (pintype "bidirectional"))
      (node (ref "GDT7") (pin "C") (pinfunction "C_C") (pintype "bidirectional"))
      (node (ref "GDT8") (pin "C") (pinfunction "C_C") (pintype "bidirectional"))
      (node (ref "J1") (pin "S1") (pinfunction "S1_S1") (pintype "bidirectional"))
      (node (ref "J1") (pin "S2") (pinfunction "S2_S2") (pintype "bidirectional"))
      (node (ref "J2") (pin "S1") (pinfunction "S1_S1") (pintype "bidirectional"))
      (node (ref "J2") (pin "S2") (pinfunction "S2_S2") (pintype "bidirectional"))
      (node (ref "J3") (pin "P$1") (pinfunction "P$1_P$1") (pintype "bidirectional"))
      (node (ref "J3") (pin "P$2") (pinfunction "P$2_P$2") (pintype "bidirectional"))
      (node (ref "J3") (pin "P$3") (pinfunction "P$3_P$3") (pintype "bidirectional"))
      (node (ref "J3") (pin "P$4") (pinfunction "P$4_P$4") (pintype "bidirectional"))
      (node (ref "J4") (pin "2") (pinfunction "GND_2") (pintype "bidirectional"))
      (node (ref "R34") (pin "1") (pinfunction "1_1") (pintype "passive"))
      (node (ref "R44") (pin "1") (pinfunction "1_1") (pintype "passive"))
      (node (ref "R54") (pin "1") (pinfunction "1_1") (pintype "passive"))
      (node (ref "R7") (pin "1") (pinfunction "1_1") (pintype "passive"))
      (node (ref "R8") (pin "2") (pinfunction "2_2") (pintype "passive"))
    )
    (net (code "110") (name "SWGND") (class "Default")
      (node (ref "U7") (pin "42") (pinfunction "SWGND_42") (pintype "power_in"))
    )
    (net (code "111") (name "V+") (class "Default")
      (node (ref "CR1") (pin "K") (pinfunction "K_K") (pintype "bidirectional"))
      (node (ref "F1") (pin "2") (pinfunction "P$2_2") (pintype "bidirectional"))
      (node (ref "F2") (pin "2") (pinfunction "P$2_2") (pintype "bidirectional"))
      (node (ref "F3") (pin "2") (pinfunction "P$2_2") (pintype "bidirectional"))
      (node (ref "F4") (pin "2") (pinfunction "P$2_2") (pintype "bidirectional"))
      (node (ref "R29") (pin "2") (pinfunction "2_2") (pintype "passive"))
    )
    (net (code "112") (name "VBUS") (class "Default")
      (node (ref "U7") (pin "40") (pinfunction "VBUS_40") (pintype "power_in"))
    )
    (net (code "113") (name "VMID") (class "Default")
      (node (ref "C1") (pin "1") (pinfunction "1_1") (pintype "passive"))
      (node (ref "C17") (pin "1") (pinfunction "1_1") (pintype "passive"))
      (node (ref "C24") (pin "1") (pinfunction "1_1") (pintype "passive"))
      (node (ref "C31") (pin "1") (pinfunction "1_1") (pintype "passive"))
      (node (ref "R18") (pin "1") (pinfunction "1_1") (pintype "passive"))
      (node (ref "R19") (pin "2") (pinfunction "2_2") (pintype "passive"))
      (node (ref "T2") (pin "5") (pinfunction "5_5") (pintype "bidirectional"))
      (node (ref "T4") (pin "5") (pinfunction "5_5") (pintype "bidirectional"))
      (node (ref "T6") (pin "5") (pinfunction "5_5") (pintype "bidirectional"))
      (node (ref "T8") (pin "5") (pinfunction "5_5") (pintype "bidirectional"))
    )
    (net (code "114") (name "VSYS") (class "Default")
      (node (ref "U7") (pin "39") (pinfunction "VSYS_39") (pintype "power_in"))
    )
    (net (code "115") (name "unconnected-(J4-NO-Pad3)") (class "Default")
      (node (ref "J4") (pin "3") (pinfunction "NO_3") (pintype "bidirectional"))
    )
    (net (code "116") (name "unconnected-(J5-DAT1-PadP8)") (class "Default")
      (node (ref "J5") (pin "P8") (pinfunction "DAT1_P8") (pintype "bidirectional"))
    )
    (net (code "117") (name "unconnected-(J5-DAT2-PadP1)") (class "Default")
      (node (ref "J5") (pin "P1") (pinfunction "DAT2_P1") (pintype "bidirectional"))
    )
    (net (code "118") (name "unconnected-(T1-Pad5)") (class "Default")
      (node (ref "T1") (pin "5") (pinfunction "5_5") (pintype "bidirectional"))
    )
    (net (code "119") (name "unconnected-(T3-Pad5)") (class "Default")
      (node (ref "T3") (pin "5") (pinfunction "5_5") (pintype "bidirectional"))
    )
    (net (code "120") (name "unconnected-(T5-Pad5)") (class "Default")
      (node (ref "T5") (pin "5") (pinfunction "5_5") (pintype "bidirectional"))
    )
    (net (code "121") (name "unconnected-(T7-Pad5)") (class "Default")
      (node (ref "T7") (pin "5") (pinfunction "5_5") (pintype "bidirectional"))
    )
    (net (code "122") (name "unconnected-(U7-3V3_EN-Pad37)") (class "Default")
      (node (ref "U7") (pin "37") (pinfunction "3V3_EN_37") (pintype "input"))
    )
    (net (code "123") (name "unconnected-(U7-ADC_REF-Pad35)") (class "Default")
      (node (ref "U7") (pin "35") (pinfunction "ADC_REF_35") (pintype "input"))
    )
    (net (code "124") (name "unconnected-(U7-RUN-Pad30)") (class "Default")
      (node (ref "U7") (pin "30") (pinfunction "RUN_30") (pintype "input"))
    )
    (net (code "125") (name "unconnected-(U7-SWCLK-Pad41)") (class "Default")
      (node (ref "U7") (pin "41") (pinfunction "SWCLK_41") (pintype "input"))
    )
    (net (code "126") (name "unconnected-(U7-SWDIO-Pad43)") (class "Default")
      (node (ref "U7") (pin "43") (pinfunction "SWDIO_43") (pintype "bidirectional"))
    )
  )
)
